# design.net
KiCad netlist of a schematic drawn in Altium Designer
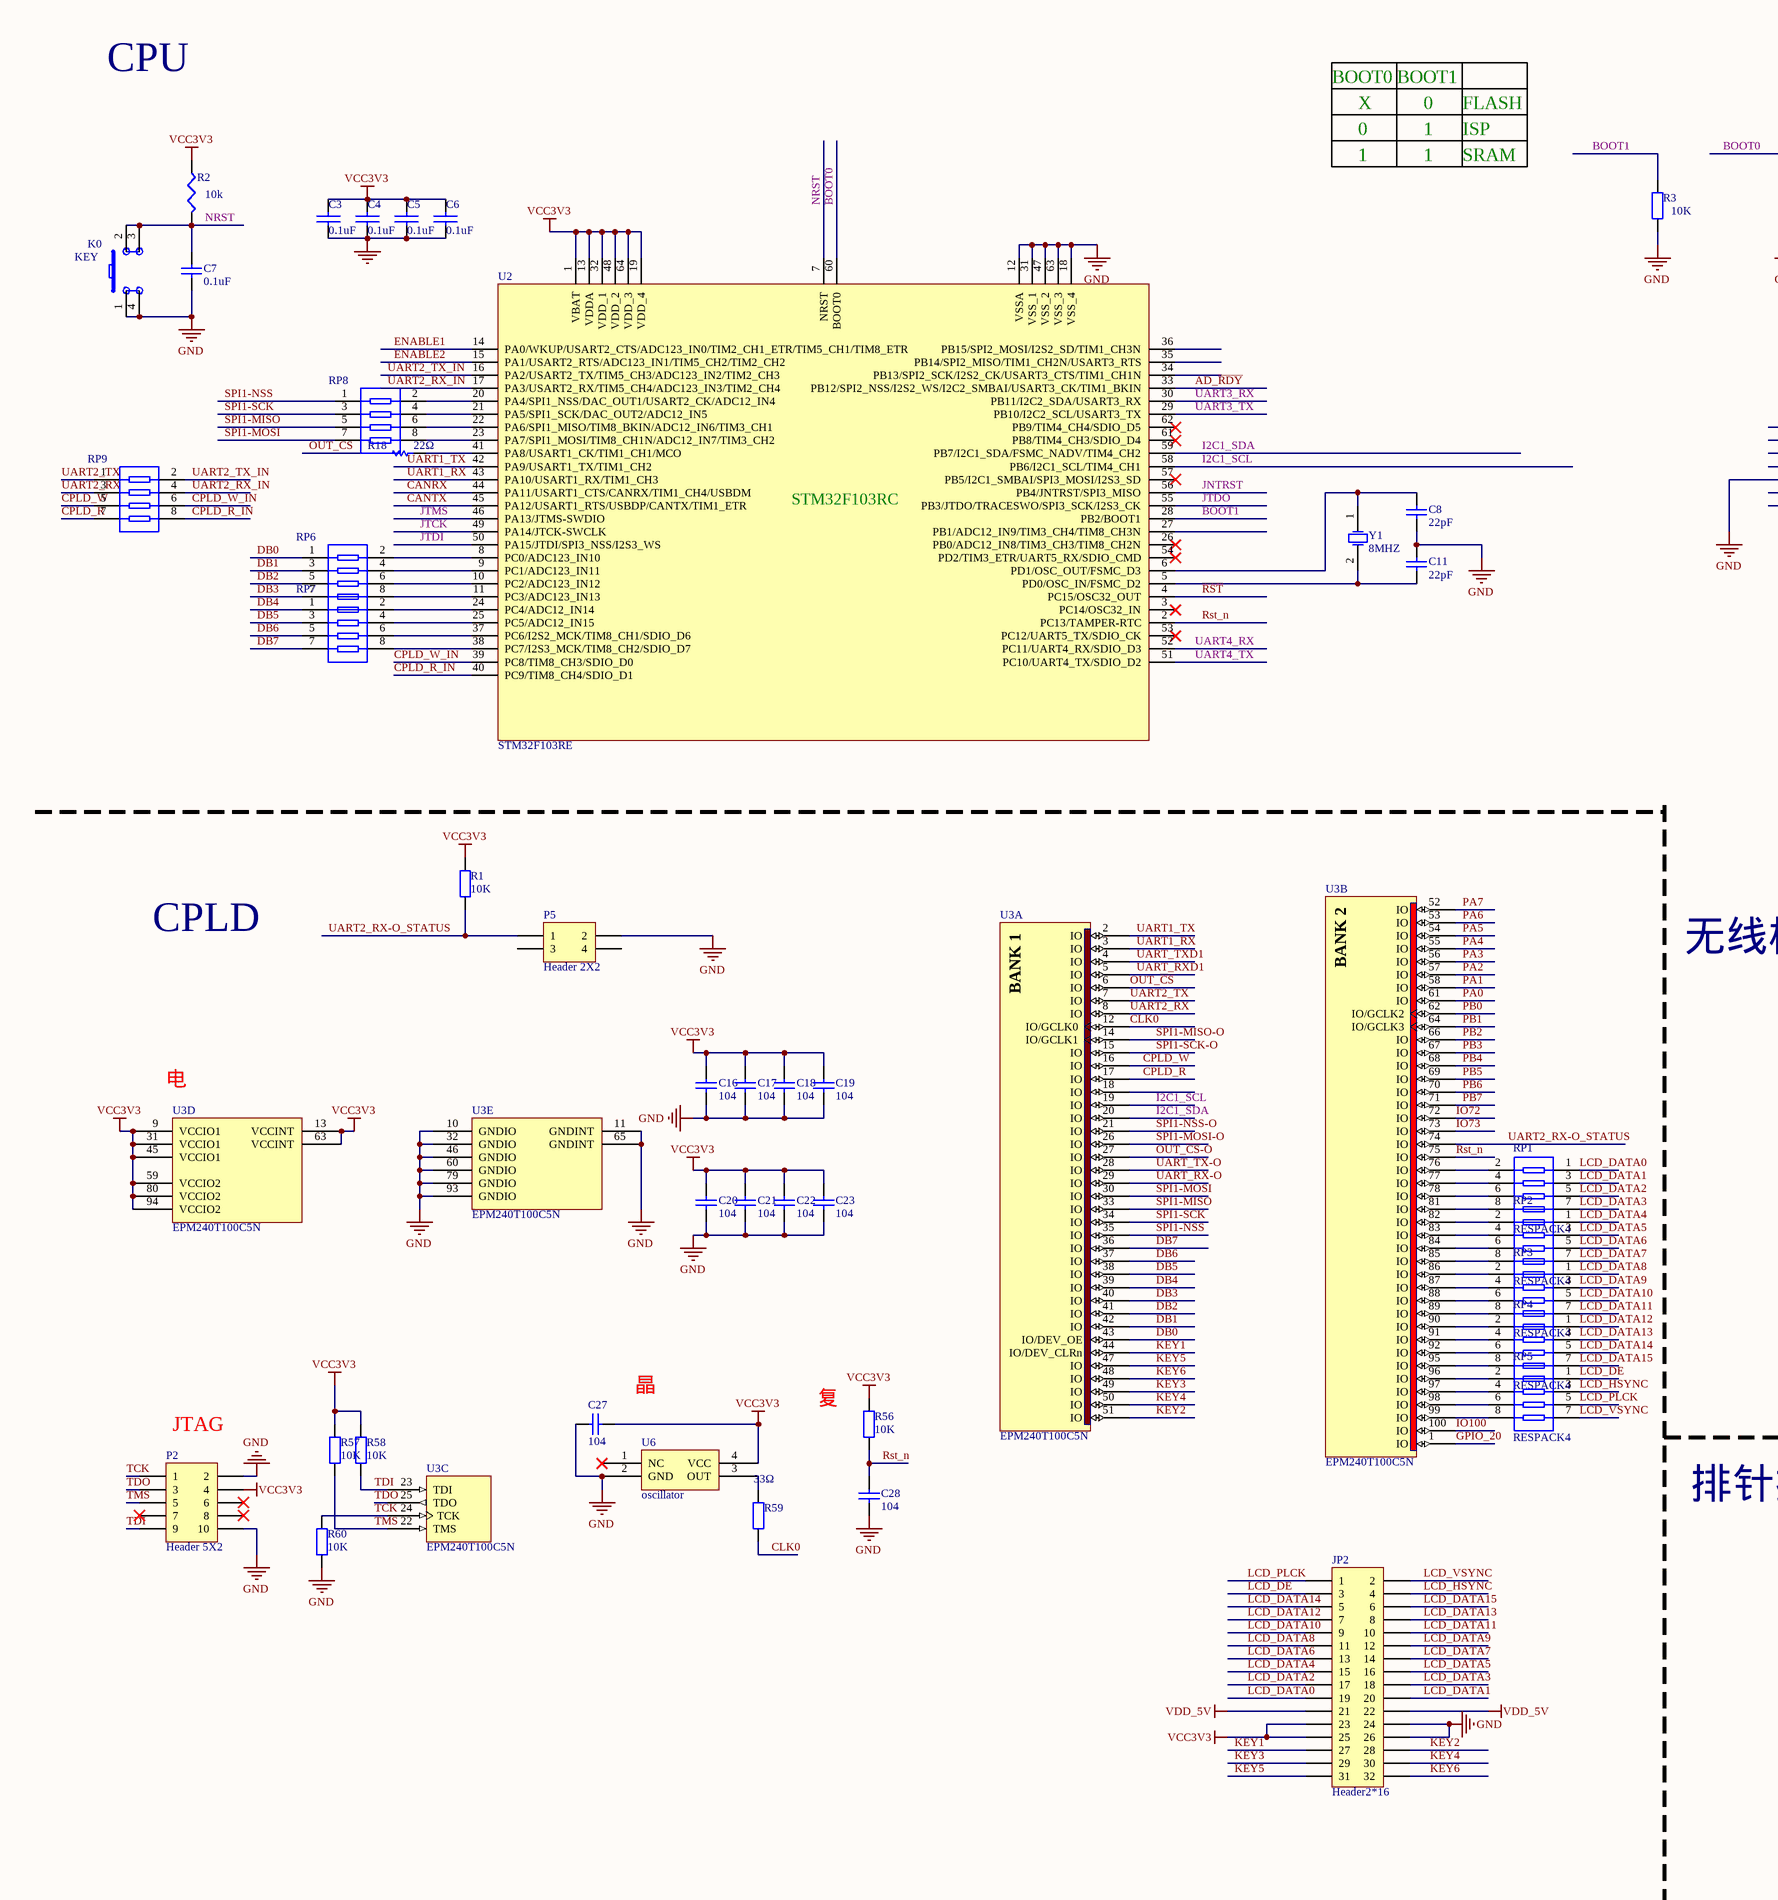
[diagram p0: 控制板.SchDoc, left]
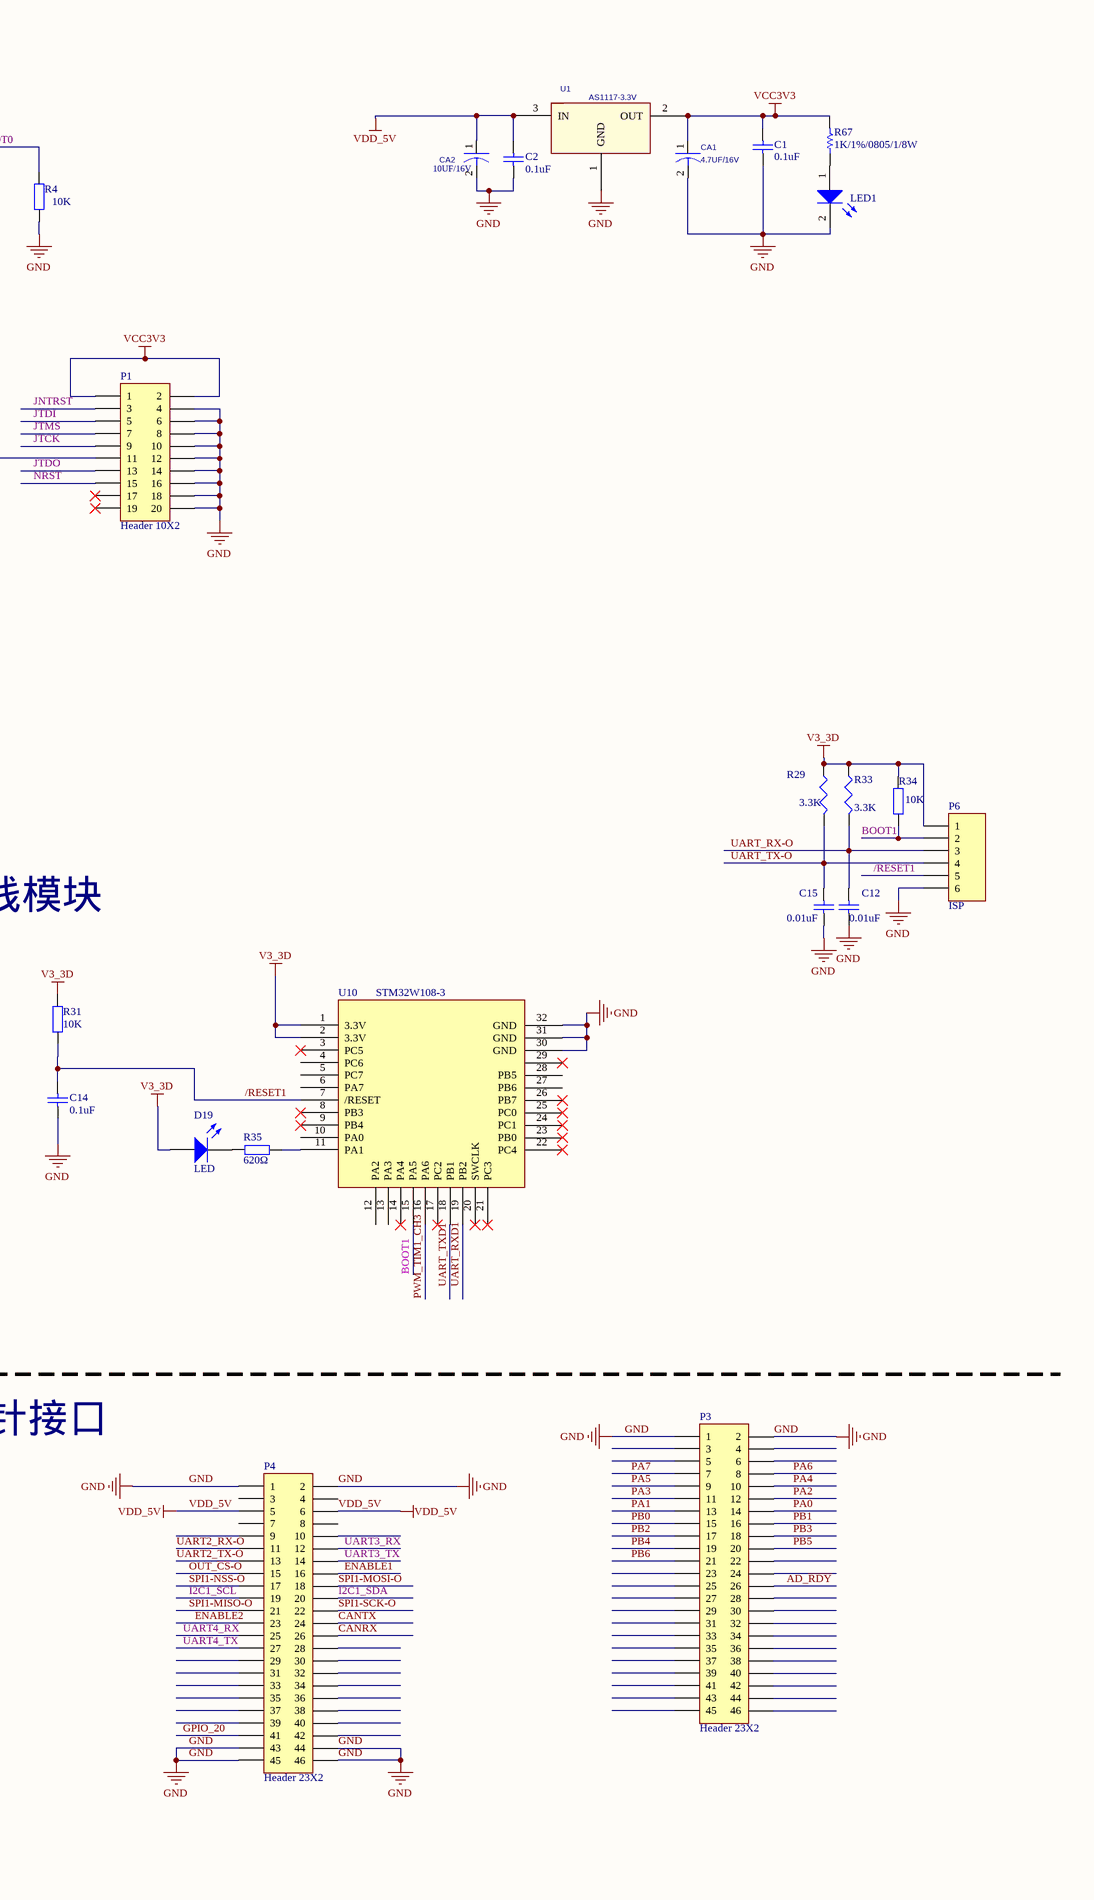
[diagram p1: 控制板.SchDoc, right]

(export (version "E")
  (design (tool "Eeschema 10.0.6"))
  (components
    (comp (ref "C1")
      (value "0.1uF")
      (footprint "C0805")
      (description "Capacitor")
      (fields (field (name "PUBLISHER") "Altium Limited"))
      (libsource (lib "Miscellaneous Devices") (part "Cap"))
    )
    (comp (ref "C2")
      (value "0.1uF")
      (footprint "C0805")
      (description "Capacitor")
      (fields (field (name "PUBLISHER") "Altium Limited"))
      (libsource (lib "Miscellaneous Devices") (part "Cap"))
    )
    (comp (ref "C3")
      (value "0.1uF")
      (footprint "C0805")
      (description "Capacitor")
      (libsource (lib "*") (part "Cap"))
    )
    (comp (ref "C4")
      (value "0.1uF")
      (footprint "C0805")
      (description "Capacitor")
      (libsource (lib "*") (part "Cap"))
    )
    (comp (ref "C5")
      (value "0.1uF")
      (footprint "C0805")
      (description "Capacitor")
      (libsource (lib "*") (part "Cap"))
    )
    (comp (ref "C6")
      (value "0.1uF")
      (footprint "C0805")
      (description "Capacitor")
      (libsource (lib "*") (part "Cap"))
    )
    (comp (ref "C7")
      (value "0.1uF")
      (footprint "C0805")
      (description "Capacitor")
      (fields (field (name "PUBLISHER") "Altium Limited"))
      (libsource (lib "Miscellaneous Devices") (part "Cap"))
    )
    (comp (ref "C8")
      (value "22pF")
      (footprint "C0805")
      (description "Capacitor")
      (fields (field (name "PUBLISHER") "Altium Limited"))
      (libsource (lib "Miscellaneous Devices") (part "Cap"))
    )
    (comp (ref "C11")
      (value "22pF")
      (footprint "C0805")
      (description "Capacitor")
      (fields (field (name "PUBLISHER") "Altium Limited"))
      (libsource (lib "Miscellaneous Devices") (part "Cap"))
    )
    (comp (ref "C12")
      (value "0.01uF")
      (footprint "C0805")
      (description "Capacitor")
      (fields (field (name "PUBLISHER") "Altium Limited"))
      (libsource (lib "Miscellaneous Devices") (part "Cap"))
    )
    (comp (ref "C14")
      (value "0.1uF")
      (footprint "C0805")
      (description "Capacitor")
      (fields (field (name "PUBLISHER") "Altium Limited"))
      (libsource (lib "Miscellaneous Devices") (part "Cap"))
    )
    (comp (ref "C15")
      (value "0.01uF")
      (footprint "C0805")
      (description "Capacitor")
      (fields (field (name "PUBLISHER") "Altium Limited"))
      (libsource (lib "Miscellaneous Devices") (part "Cap"))
    )
    (comp (ref "C16")
      (value "104")
      (footprint "C0805")
      (description "Capacitor")
      (fields (field (name "Comment") "0.1uF") (field (name "PUBLISHER") "Altium Limited"))
      (libsource (lib "Miscellaneous Devices") (part "Cap"))
    )
    (comp (ref "C17")
      (value "104")
      (footprint "C0805")
      (description "Capacitor")
      (fields (field (name "Comment") "0.1uF") (field (name "PUBLISHER") "Altium Limited"))
      (libsource (lib "Miscellaneous Devices") (part "Cap"))
    )
    (comp (ref "C18")
      (value "104")
      (footprint "C0805")
      (description "Capacitor")
      (fields (field (name "Comment") "0.1uF") (field (name "PUBLISHER") "Altium Limited"))
      (libsource (lib "Miscellaneous Devices") (part "Cap"))
    )
    (comp (ref "C19")
      (value "104")
      (footprint "C0805")
      (description "Capacitor")
      (fields (field (name "Comment") "0.1uF") (field (name "PUBLISHER") "Altium Limited"))
      (libsource (lib "Miscellaneous Devices") (part "Cap"))
    )
    (comp (ref "C20")
      (value "104")
      (footprint "C0805")
      (description "Capacitor")
      (fields (field (name "Comment") "0.1uF") (field (name "PUBLISHER") "Altium Limited"))
      (libsource (lib "Miscellaneous Devices") (part "Cap"))
    )
    (comp (ref "C21")
      (value "104")
      (footprint "C0805")
      (description "Capacitor")
      (fields (field (name "Comment") "0.1uF") (field (name "PUBLISHER") "Altium Limited"))
      (libsource (lib "Miscellaneous Devices") (part "Cap"))
    )
    (comp (ref "C22")
      (value "104")
      (footprint "C0805")
      (description "Capacitor")
      (fields (field (name "Comment") "0.1uF") (field (name "PUBLISHER") "Altium Limited"))
      (libsource (lib "Miscellaneous Devices") (part "Cap"))
    )
    (comp (ref "C23")
      (value "104")
      (footprint "C0805")
      (description "Capacitor")
      (fields (field (name "Comment") "0.1uF") (field (name "PUBLISHER") "Altium Limited"))
      (libsource (lib "Miscellaneous Devices") (part "Cap"))
    )
    (comp (ref "C27")
      (value "104")
      (footprint "C0805")
      (description "Capacitor")
      (fields (field (name "Comment") "0.1uF") (field (name "PUBLISHER") "Altium Limited"))
      (libsource (lib "Miscellaneous Devices") (part "Cap"))
    )
    (comp (ref "C28")
      (value "104")
      (footprint "C0805")
      (description "Capacitor")
      (fields (field (name "Comment") "0.1uF") (field (name "PUBLISHER") "Altium Limited"))
      (libsource (lib "Miscellaneous Devices") (part "Cap"))
    )
    (comp (ref "CA1") (value "4.7UF/16V") (footprint "3528cap") (libsource (lib "v3") (part "ECAP")))
    (comp (ref "CA2") (value "10UF/16V") (footprint "3528cap") (libsource (lib "v3") (part "ECAP")))
    (comp (ref "D19")
      (value "LED")
      (footprint "0805LED")
      (description "Typical BLUE SiC LED")
      (fields (field (name "PUBLISHER") "Altium Limited"))
      (libsource (lib "Miscellaneous Devices") (part "LED3"))
    )
    (comp (ref "JP2")
      (value "Header2*16")
      (footprint "PIN-S-2.54-2*16")
      (libsource (lib "SCHLIBRARIES") (part "Header2*16"))
    )
    (comp (ref "K0") (value "KEY") (footprint "KEY-DIP") (libsource (lib "Haze") (part "KEY")))
    (comp (ref "LED1")
      (value "0805/Green")
      (footprint "LED-0805")
      (fields (field (name "PART NUMBER") "ASD-0012AA"))
      (libsource (lib "浙江关西电机数据库") (part "LED"))
    )
    (comp (ref "P1")
      (value "Header 10X2")
      (footprint "IDC-20")
      (description "Header, 10-Pin, Dual row")
      (fields (field (name "PUBLISHER") "Altium Limited"))
      (libsource (lib "Miscellaneous Connectors") (part "Header 10X2"))
    )
    (comp (ref "P2")
      (value "Header 5X2")
      (footprint "IDC-10")
      (description "Header, 5-Pin, Dual row")
      (fields (field (name "PUBLISHER") "Altium Limited"))
      (libsource (lib "Miscellaneous Connectors") (part "Header 5X2"))
    )
    (comp (ref "P3")
      (value "Header 23X2")
      (footprint "HDR2X23")
      (description "Header, 23-Pin, Dual row")
      (fields (field (name "PUBLISHER") "Altium Limited"))
      (libsource (lib "dolphi_ecs") (part "Header 23X2"))
    )
    (comp (ref "P4")
      (value "Header 23X2")
      (footprint "HDR2X23")
      (description "Header, 23-Pin, Dual row")
      (fields (field (name "PUBLISHER") "Altium Limited"))
      (libsource (lib "dolphi_ecs") (part "Header 23X2"))
    )
    (comp (ref "P5")
      (value "Header 2X2")
      (footprint "SOP4")
      (description "拨码开关")
      (fields (field (name "PUBLISHER") "Altium Limited"))
      (libsource (lib "Miscellaneous Connectors") (part "Header 2X2"))
    )
    (comp (ref "P6")
      (value "ISP")
      (footprint "SIP-6B")
      (description "Header 6X1")
      (fields (field (name "PUBLISHER") "Altium Limited"))
      (libsource (lib "Miscellaneous Connectors") (part "Header 6"))
    )
    (comp (ref "R1")
      (value "10K")
      (footprint "R0805")
      (description "Resistor")
      (fields (field (name "PUBLISHER") "Altium Limited"))
      (libsource (lib "Miscellaneous Devices") (part "Res2"))
    )
    (comp (ref "R2")
      (value "10k")
      (footprint "R0805")
      (description "Resistor")
      (fields (field (name "PUBLISHER") "Altium Limited"))
      (libsource (lib "Miscellaneous Devices") (part "Res3"))
    )
    (comp (ref "R3")
      (value "10K")
      (footprint "R0805")
      (description "Resistor")
      (fields (field (name "PUBLISHER") "Altium Limited"))
      (libsource (lib "Miscellaneous Devices") (part "Res2"))
    )
    (comp (ref "R4")
      (value "10K")
      (footprint "R0805")
      (description "Resistor")
      (fields (field (name "PUBLISHER") "Altium Limited"))
      (libsource (lib "Miscellaneous Devices") (part "Res2"))
    )
    (comp (ref "R18")
      (value "22Ω")
      (footprint "R0805")
      (description "Semiconductor Resistor")
      (fields (field (name "PUBLISHER") "Altium Limited"))
      (libsource (lib "Miscellaneous Devices") (part "Res Semi"))
    )
    (comp (ref "R29")
      (value "3.3K")
      (footprint "R0805")
      (description "Resistor")
      (fields (field (name "PUBLISHER") "Altium Limited"))
      (libsource (lib "Miscellaneous Devices") (part "Res3"))
    )
    (comp (ref "R31")
      (value "10K")
      (footprint "0805")
      (description "Resistor")
      (fields (field (name "PUBLISHER") "Altium Limited"))
      (libsource (lib "Miscellaneous Devices") (part "Res2"))
    )
    (comp (ref "R33")
      (value "3.3K")
      (footprint "R0805")
      (description "Resistor")
      (fields (field (name "PUBLISHER") "Altium Limited"))
      (libsource (lib "Miscellaneous Devices") (part "Res3"))
    )
    (comp (ref "R34")
      (value "10K")
      (footprint "R0805")
      (description "Resistor")
      (fields (field (name "PUBLISHER") "Altium Limited"))
      (libsource (lib "Miscellaneous Devices") (part "Res2"))
    )
    (comp (ref "R35")
      (value "620Ω")
      (footprint "R0805")
      (description "R")
      (libsource (lib "Haze") (part "RES"))
    )
    (comp (ref "R56")
      (value "10K")
      (footprint "R0805")
      (description "Resistor")
      (fields (field (name "PUBLISHER") "Altium Limited"))
      (libsource (lib "Miscellaneous Devices") (part "Res2"))
    )
    (comp (ref "R57")
      (value "10K")
      (footprint "R0805")
      (description "Resistor")
      (fields (field (name "PUBLISHER") "Altium Limited"))
      (libsource (lib "Miscellaneous Devices") (part "Res2"))
    )
    (comp (ref "R58")
      (value "10K")
      (footprint "R0805")
      (description "Resistor")
      (fields (field (name "PUBLISHER") "Altium Limited"))
      (libsource (lib "Miscellaneous Devices") (part "Res2"))
    )
    (comp (ref "R59")
      (value "33Ω")
      (footprint "R0805")
      (description "Resistor")
      (fields (field (name "PUBLISHER") "Altium Limited"))
      (libsource (lib "Miscellaneous Devices") (part "Res2"))
    )
    (comp (ref "R60")
      (value "10K")
      (footprint "R0805")
      (description "Resistor")
      (fields (field (name "PUBLISHER") "Altium Limited"))
      (libsource (lib "Miscellaneous Devices") (part "Res2"))
    )
    (comp (ref "R67")
      (value "1K/1%/0805/1/8W")
      (footprint "R-0805")
      (fields (field (name "PART NUMBER") "ASR-0058AA"))
      (libsource (lib "浙江关西电机数据库") (part "RES_1"))
    )
    (comp (ref "RP1")
      (value "RESPACK4")
      (footprint "8P4R_0603")
      (description "22Ω")
      (libsource (lib "*") (part "RESPACK4"))
    )
    (comp (ref "RP2")
      (value "RESPACK4")
      (footprint "8P4R_0603")
      (description "22Ω")
      (libsource (lib "*") (part "RESPACK4"))
    )
    (comp (ref "RP3")
      (value "RESPACK4")
      (footprint "8P4R_0603")
      (description "22Ω")
      (libsource (lib "*") (part "RESPACK4"))
    )
    (comp (ref "RP4")
      (value "RESPACK4")
      (footprint "8P4R_0603")
      (description "22Ω")
      (libsource (lib "*") (part "RESPACK4"))
    )
    (comp (ref "RP5")
      (value "RESPACK4")
      (footprint "8P4R_0603")
      (description "22Ω")
      (libsource (lib "*") (part "RESPACK4"))
    )
    (comp (ref "RP6")
      (value "RESPACK4")
      (footprint "8P4R_0603")
      (description "22Ω")
      (libsource (lib "*") (part "RESPACK4"))
    )
    (comp (ref "RP7")
      (value "RESPACK4")
      (footprint "8P4R_0603")
      (description "22Ω")
      (libsource (lib "*") (part "RESPACK4"))
    )
    (comp (ref "RP8")
      (value "RESPACK4")
      (footprint "8P4R_0603")
      (description "22Ω")
      (libsource (lib "*") (part "RESPACK4"))
    )
    (comp (ref "RP9")
      (value "RESPACK4")
      (footprint "8P4R_0603")
      (description "22Ω")
      (libsource (lib "*") (part "RESPACK4"))
    )
    (comp (ref "U1") (value "AS1117-3.3V") (libsource (lib "v3") (part "AS1117")))
    (comp (ref "U2") (value "STM32F103RE") (footprint "LQFP64") (libsource (lib "MXJ") (part "STM32F103RE")))
    (comp (ref "U3")
      (value "EPM240T100C5N")
      (footprint "TQFP100_N")
      (fields (field (name "PUBLISHER") "Altium Limited"))
      (libsource (lib "Altera MAX II") (part "EPM240GT100C5N"))
    )
    (comp (ref "U6")
      (value "oscillator")
      (footprint "JZ-5032")
      (libsource (lib "Schlib1") (part "oscillator"))
    )
    (comp (ref "U10")
      (value "STM32W108-3")
      (footprint "STM32W108-3")
      (libsource (lib "STM32W108-3") (part "STM32W108-3"))
    )
    (comp (ref "Y1")
      (value "8MHZ")
      (footprint "XTAL")
      (description "Crystal Oscillator")
      (fields (field (name "PUBLISHER") "Altium Limited"))
      (libsource (lib "Miscellaneous Devices") (part "XTAL"))
    )
  )
  (nets
    (net (code "2") (name "/AD_~{RDY}") (class "Default")
      (node (ref "P3") (pin "26") (pinfunction "26_26") (pintype "passive"))
      (node (ref "U2") (pin "33") (pinfunction "PB12/SPI2_NSS/I2S2_WS/I2C2_SMBAI/USART3_CK/TIM1_BKIN_33") (pintype "passive"))
    )
    (net (code "3") (name "/BOOT0") (class "Default")
      (node (ref "R4") (pin "2") (pinfunction "2_2") (pintype "passive"))
      (node (ref "U2") (pin "60") (pinfunction "BOOT0_60") (pintype "passive"))
    )
    (net (code "4") (name "/BOOT1") (class "Default")
      (node (ref "P6") (pin "2") (pinfunction "2_2") (pintype "passive"))
      (node (ref "R3") (pin "2") (pinfunction "2_2") (pintype "passive"))
      (node (ref "R34") (pin "1") (pinfunction "1_1") (pintype "passive"))
      (node (ref "U10") (pin "15") (pinfunction "PA5_15") (pintype "passive"))
      (node (ref "U2") (pin "28") (pinfunction "PB2/BOOT1_28") (pintype "passive"))
    )
    (net (code "5") (name "/CANRX") (class "Default")
      (node (ref "P4") (pin "26") (pinfunction "26_26") (pintype "passive"))
      (node (ref "U2") (pin "44") (pinfunction "PA11/USART1_CTS/CANRX/TIM1_CH4/USBDM_44") (pintype "passive"))
    )
    (net (code "6") (name "/CANTX") (class "Default")
      (node (ref "P4") (pin "24") (pinfunction "24_24") (pintype "passive"))
      (node (ref "U2") (pin "45") (pinfunction "PA12/USART1_RTS/USBDP/CANTX/TIM1_ETR_45") (pintype "passive"))
    )
    (net (code "7") (name "/CLK0") (class "Default")
      (node (ref "R59") (pin "1") (pinfunction "1_1") (pintype "passive"))
      (node (ref "U3") (pin "12") (pinfunction "IO/GCLK0_12") (pintype "bidirectional"))
    )
    (net (code "8") (name "/CPLD_R") (class "Default")
      (node (ref "RP9") (pin "7") (pinfunction "7_7") (pintype "passive"))
      (node (ref "U3") (pin "17") (pinfunction "IO_17") (pintype "bidirectional"))
    )
    (net (code "9") (name "/CPLD_R_IN") (class "Default")
      (node (ref "RP9") (pin "8") (pinfunction "8_8") (pintype "passive"))
      (node (ref "U2") (pin "40") (pinfunction "PC9/TIM8_CH4/SDIO_D1_40") (pintype "passive"))
    )
    (net (code "10") (name "/CPLD_W") (class "Default")
      (node (ref "RP9") (pin "5") (pinfunction "5_5") (pintype "passive"))
      (node (ref "U3") (pin "16") (pinfunction "IO_16") (pintype "bidirectional"))
    )
    (net (code "11") (name "/CPLD_W_IN") (class "Default")
      (node (ref "RP9") (pin "6") (pinfunction "6_6") (pintype "passive"))
      (node (ref "U2") (pin "39") (pinfunction "PC8/TIM8_CH3/SDIO_D0_39") (pintype "passive"))
    )
    (net (code "12") (name "/DB0") (class "Default")
      (node (ref "RP6") (pin "1") (pinfunction "1_1") (pintype "passive"))
      (node (ref "U3") (pin "43") (pinfunction "IO/DEV_OE_43") (pintype "bidirectional"))
    )
    (net (code "13") (name "/DB1") (class "Default")
      (node (ref "RP6") (pin "3") (pinfunction "3_3") (pintype "passive"))
      (node (ref "U3") (pin "42") (pinfunction "IO_42") (pintype "bidirectional"))
    )
    (net (code "14") (name "/DB2") (class "Default")
      (node (ref "RP6") (pin "5") (pinfunction "5_5") (pintype "passive"))
      (node (ref "U3") (pin "41") (pinfunction "IO_41") (pintype "bidirectional"))
    )
    (net (code "15") (name "/DB3") (class "Default")
      (node (ref "RP6") (pin "7") (pinfunction "7_7") (pintype "passive"))
      (node (ref "U3") (pin "40") (pinfunction "IO_40") (pintype "bidirectional"))
    )
    (net (code "16") (name "/DB4") (class "Default")
      (node (ref "RP7") (pin "1") (pinfunction "1_1") (pintype "passive"))
      (node (ref "U3") (pin "39") (pinfunction "IO_39") (pintype "bidirectional"))
    )
    (net (code "17") (name "/DB5") (class "Default")
      (node (ref "RP7") (pin "3") (pinfunction "3_3") (pintype "passive"))
      (node (ref "U3") (pin "38") (pinfunction "IO_38") (pintype "bidirectional"))
    )
    (net (code "18") (name "/DB6") (class "Default")
      (node (ref "RP7") (pin "5") (pinfunction "5_5") (pintype "passive"))
      (node (ref "U3") (pin "37") (pinfunction "IO_37") (pintype "bidirectional"))
    )
    (net (code "19") (name "/DB7") (class "Default")
      (node (ref "RP7") (pin "7") (pinfunction "7_7") (pintype "passive"))
      (node (ref "U3") (pin "36") (pinfunction "IO_36") (pintype "bidirectional"))
    )
    (net (code "20") (name "/ENABLE1") (class "Default")
      (node (ref "P4") (pin "16") (pinfunction "16_16") (pintype "passive"))
      (node (ref "U2") (pin "14") (pinfunction "PA0/WKUP/USART2_CTS/ADC123_IN0/TIM2_CH1_ETR/TIM5_CH1/TIM8_ETR_14") (pintype "passive"))
    )
    (net (code "21") (name "/ENABLE2") (class "Default")
      (node (ref "P4") (pin "23") (pinfunction "23_23") (pintype "passive"))
      (node (ref "U2") (pin "15") (pinfunction "PA1/USART2_RTS/ADC123_IN1/TIM5_CH2/TIM2_CH2_15") (pintype "passive"))
    )
    (net (code "22") (name "/GPIO_20") (class "Default")
      (node (ref "P4") (pin "41") (pinfunction "41_41") (pintype "passive"))
      (node (ref "U3") (pin "1") (pinfunction "IO_1") (pintype "bidirectional"))
    )
    (net (code "23") (name "/I2C1_SCL") (class "Default")
      (node (ref "P4") (pin "19") (pinfunction "19_19") (pintype "passive"))
      (node (ref "U2") (pin "58") (pinfunction "PB6/I2C1_SCL/TIM4_CH1_58") (pintype "passive"))
      (node (ref "U3") (pin "19") (pinfunction "IO_19") (pintype "bidirectional"))
    )
    (net (code "24") (name "/I2C1_SDA") (class "Default")
      (node (ref "P4") (pin "20") (pinfunction "20_20") (pintype "passive"))
      (node (ref "U2") (pin "59") (pinfunction "PB7/I2C1_SDA/FSMC_NADV/TIM4_CH2_59") (pintype "passive"))
      (node (ref "U3") (pin "20") (pinfunction "IO_20") (pintype "bidirectional"))
    )
    (net (code "25") (name "/IO72") (class "Default")
      (node (ref "U3") (pin "72") (pinfunction "IO_72") (pintype "bidirectional"))
    )
    (net (code "26") (name "/IO73") (class "Default")
      (node (ref "U3") (pin "73") (pinfunction "IO_73") (pintype "bidirectional"))
    )
    (net (code "27") (name "/IO100") (class "Default")
      (node (ref "U3") (pin "100") (pinfunction "IO_100") (pintype "bidirectional"))
    )
    (net (code "28") (name "/JNTRST") (class "Default")
      (node (ref "P1") (pin "3") (pinfunction "3_3") (pintype "passive"))
      (node (ref "U2") (pin "56") (pinfunction "PB4/JNTRST/SPI3_MISO_56") (pintype "passive"))
    )
    (net (code "29") (name "/JTCK") (class "Default")
      (node (ref "P1") (pin "9") (pinfunction "9_9") (pintype "passive"))
      (node (ref "U2") (pin "49") (pinfunction "PA14/JTCK-SWCLK_49") (pintype "passive"))
    )
    (net (code "30") (name "/JTDI") (class "Default")
      (node (ref "P1") (pin "5") (pinfunction "5_5") (pintype "passive"))
      (node (ref "U2") (pin "50") (pinfunction "PA15/JTDI/SPI3_NSS/I2S3_WS_50") (pintype "passive"))
    )
    (net (code "31") (name "/JTDO") (class "Default")
      (node (ref "P1") (pin "13") (pinfunction "13_13") (pintype "passive"))
      (node (ref "U2") (pin "55") (pinfunction "PB3/JTDO/TRACESWO/SPI3_SCK/I2S3_CK_55") (pintype "passive"))
    )
    (net (code "32") (name "/JTMS") (class "Default")
      (node (ref "P1") (pin "7") (pinfunction "7_7") (pintype "passive"))
      (node (ref "U2") (pin "46") (pinfunction "PA13/JTMS-SWDIO_46") (pintype "passive"))
    )
    (net (code "33") (name "/KEY1") (class "Default")
      (node (ref "JP2") (pin "27") (pinfunction "27_27") (pintype "passive"))
      (node (ref "U3") (pin "44") (pinfunction "IO/DEV_CLRn_44") (pintype "bidirectional"))
    )
    (net (code "34") (name "/KEY2") (class "Default")
      (node (ref "JP2") (pin "28") (pinfunction "28_28") (pintype "passive"))
      (node (ref "U3") (pin "51") (pinfunction "IO_51") (pintype "bidirectional"))
    )
    (net (code "35") (name "/KEY3") (class "Default")
      (node (ref "JP2") (pin "29") (pinfunction "29_29") (pintype "passive"))
      (node (ref "U3") (pin "49") (pinfunction "IO_49") (pintype "bidirectional"))
    )
    (net (code "36") (name "/KEY4") (class "Default")
      (node (ref "JP2") (pin "30") (pinfunction "30_30") (pintype "passive"))
      (node (ref "U3") (pin "50") (pinfunction "IO_50") (pintype "bidirectional"))
    )
    (net (code "37") (name "/KEY5") (class "Default")
      (node (ref "JP2") (pin "31") (pinfunction "31_31") (pintype "passive"))
      (node (ref "U3") (pin "47") (pinfunction "IO_47") (pintype "bidirectional"))
    )
    (net (code "38") (name "/KEY6") (class "Default")
      (node (ref "JP2") (pin "32") (pinfunction "32_32") (pintype "passive"))
      (node (ref "U3") (pin "48") (pinfunction "IO_48") (pintype "bidirectional"))
    )
    (net (code "39") (name "/LCD_DATA0") (class "Default")
      (node (ref "JP2") (pin "19") (pinfunction "19_19") (pintype "passive"))
      (node (ref "RP1") (pin "1") (pinfunction "1_1") (pintype "passive"))
    )
    (net (code "40") (name "/LCD_DATA1") (class "Default")
      (node (ref "JP2") (pin "20") (pinfunction "20_20") (pintype "passive"))
      (node (ref "RP1") (pin "3") (pinfunction "3_3") (pintype "passive"))
    )
    (net (code "41") (name "/LCD_DATA2") (class "Default")
      (node (ref "JP2") (pin "17") (pinfunction "17_17") (pintype "passive"))
      (node (ref "RP1") (pin "5") (pinfunction "5_5") (pintype "passive"))
    )
    (net (code "42") (name "/LCD_DATA3") (class "Default")
      (node (ref "JP2") (pin "18") (pinfunction "18_18") (pintype "passive"))
      (node (ref "RP1") (pin "7") (pinfunction "7_7") (pintype "passive"))
    )
    (net (code "43") (name "/LCD_DATA4") (class "Default")
      (node (ref "JP2") (pin "15") (pinfunction "15_15") (pintype "passive"))
      (node (ref "RP2") (pin "1") (pinfunction "1_1") (pintype "passive"))
    )
    (net (code "44") (name "/LCD_DATA5") (class "Default")
      (node (ref "JP2") (pin "16") (pinfunction "16_16") (pintype "passive"))
      (node (ref "RP2") (pin "3") (pinfunction "3_3") (pintype "passive"))
    )
    (net (code "45") (name "/LCD_DATA6") (class "Default")
      (node (ref "JP2") (pin "13") (pinfunction "13_13") (pintype "passive"))
      (node (ref "RP2") (pin "5") (pinfunction "5_5") (pintype "passive"))
    )
    (net (code "46") (name "/LCD_DATA7") (class "Default")
      (node (ref "JP2") (pin "14") (pinfunction "14_14") (pintype "passive"))
      (node (ref "RP2") (pin "7") (pinfunction "7_7") (pintype "passive"))
    )
    (net (code "47") (name "/LCD_DATA8") (class "Default")
      (node (ref "JP2") (pin "11") (pinfunction "11_11") (pintype "passive"))
      (node (ref "RP3") (pin "1") (pinfunction "1_1") (pintype "passive"))
    )
    (net (code "48") (name "/LCD_DATA9") (class "Default")
      (node (ref "JP2") (pin "12") (pinfunction "12_12") (pintype "passive"))
      (node (ref "RP3") (pin "3") (pinfunction "3_3") (pintype "passive"))
    )
    (net (code "49") (name "/LCD_DATA10") (class "Default")
      (node (ref "JP2") (pin "9") (pinfunction "9_9") (pintype "passive"))
      (node (ref "RP3") (pin "5") (pinfunction "5_5") (pintype "passive"))
    )
    (net (code "50") (name "/LCD_DATA11") (class "Default")
      (node (ref "JP2") (pin "10") (pinfunction "10_10") (pintype "passive"))
      (node (ref "RP3") (pin "7") (pinfunction "7_7") (pintype "passive"))
    )
    (net (code "51") (name "/LCD_DATA12") (class "Default")
      (node (ref "JP2") (pin "7") (pinfunction "7_7") (pintype "passive"))
      (node (ref "RP4") (pin "1") (pinfunction "1_1") (pintype "passive"))
    )
    (net (code "52") (name "/LCD_DATA13") (class "Default")
      (node (ref "JP2") (pin "8") (pinfunction "8_8") (pintype "passive"))
      (node (ref "RP4") (pin "3") (pinfunction "3_3") (pintype "passive"))
    )
    (net (code "53") (name "/LCD_DATA14") (class "Default")
      (node (ref "JP2") (pin "5") (pinfunction "5_5") (pintype "passive"))
      (node (ref "RP4") (pin "5") (pinfunction "5_5") (pintype "passive"))
    )
    (net (code "54") (name "/LCD_DATA15") (class "Default")
      (node (ref "JP2") (pin "6") (pinfunction "6_6") (pintype "passive"))
      (node (ref "RP4") (pin "7") (pinfunction "7_7") (pintype "passive"))
    )
    (net (code "55") (name "/LCD_DE") (class "Default")
      (node (ref "JP2") (pin "3") (pinfunction "3_3") (pintype "passive"))
      (node (ref "RP5") (pin "1") (pinfunction "1_1") (pintype "passive"))
    )
    (net (code "56") (name "/LCD_HSYNC") (class "Default")
      (node (ref "JP2") (pin "4") (pinfunction "4_4") (pintype "passive"))
      (node (ref "RP5") (pin "3") (pinfunction "3_3") (pintype "passive"))
    )
    (net (code "57") (name "/LCD_PLCK") (class "Default")
      (node (ref "JP2") (pin "1") (pinfunction "1_1") (pintype "passive"))
      (node (ref "RP5") (pin "5") (pinfunction "5_5") (pintype "passive"))
    )
    (net (code "58") (name "/LCD_VSYNC") (class "Default")
      (node (ref "JP2") (pin "2") (pinfunction "2_2") (pintype "passive"))
      (node (ref "RP5") (pin "7") (pinfunction "7_7") (pintype "passive"))
    )
    (net (code "59") (name "/NRST") (class "Default")
      (node (ref "C7") (pin "2") (pinfunction "2_2") (pintype "passive"))
      (node (ref "K0") (pin "2") (pintype "passive"))
      (node (ref "K0") (pin "3") (pintype "passive"))
      (node (ref "P1") (pin "15") (pinfunction "15_15") (pintype "passive"))
      (node (ref "R2") (pin "2") (pinfunction "2_2") (pintype "passive"))
      (node (ref "U2") (pin "7") (pinfunction "NRST_7") (pintype "passive"))
    )
    (net (code "60") (name "/OUT_~{CS}") (class "Default")
      (node (ref "R18") (pin "1") (pinfunction "1_1") (pintype "passive"))
      (node (ref "U3") (pin "6") (pinfunction "IO_6") (pintype "bidirectional"))
    )
    (net (code "61") (name "/OUT_~{CS}-O") (class "Default")
      (node (ref "P4") (pin "15") (pinfunction "15_15") (pintype "passive"))
      (node (ref "U3") (pin "27") (pinfunction "IO_27") (pintype "bidirectional"))
    )
    (net (code "62") (name "/PA0") (class "Default")
      (node (ref "P3") (pin "14") (pinfunction "14_14") (pintype "passive"))
      (node (ref "U3") (pin "61") (pinfunction "IO_61") (pintype "bidirectional"))
    )
    (net (code "63") (name "/PA1") (class "Default")
      (node (ref "P3") (pin "13") (pinfunction "13_13") (pintype "passive"))
      (node (ref "U3") (pin "58") (pinfunction "IO_58") (pintype "bidirectional"))
    )
    (net (code "64") (name "/PA2") (class "Default")
      (node (ref "P3") (pin "12") (pinfunction "12_12") (pintype "passive"))
      (node (ref "U3") (pin "57") (pinfunction "IO_57") (pintype "bidirectional"))
    )
    (net (code "65") (name "/PA3") (class "Default")
      (node (ref "P3") (pin "11") (pinfunction "11_11") (pintype "passive"))
      (node (ref "U3") (pin "56") (pinfunction "IO_56") (pintype "bidirectional"))
    )
    (net (code "66") (name "/PA4") (class "Default")
      (node (ref "P3") (pin "10") (pinfunction "10_10") (pintype "passive"))
      (node (ref "U3") (pin "55") (pinfunction "IO_55") (pintype "bidirectional"))
    )
    (net (code "67") (name "/PA5") (class "Default")
      (node (ref "P3") (pin "9") (pinfunction "9_9") (pintype "passive"))
      (node (ref "U3") (pin "54") (pinfunction "IO_54") (pintype "bidirectional"))
    )
    (net (code "68") (name "/PA6") (class "Default")
      (node (ref "P3") (pin "8") (pinfunction "8_8") (pintype "passive"))
      (node (ref "U3") (pin "53") (pinfunction "IO_53") (pintype "bidirectional"))
    )
    (net (code "69") (name "/PA7") (class "Default")
      (node (ref "P3") (pin "7") (pinfunction "7_7") (pintype "passive"))
      (node (ref "U3") (pin "52") (pinfunction "IO_52") (pintype "bidirectional"))
    )
    (net (code "70") (name "/PB0") (class "Default")
      (node (ref "P3") (pin "15") (pinfunction "15_15") (pintype "passive"))
      (node (ref "U3") (pin "62") (pinfunction "IO/GCLK2_62") (pintype "bidirectional"))
    )
    (net (code "71") (name "/PB1") (class "Default")
      (node (ref "P3") (pin "16") (pinfunction "16_16") (pintype "passive"))
      (node (ref "U3") (pin "64") (pinfunction "IO/GCLK3_64") (pintype "bidirectional"))
    )
    (net (code "72") (name "/PB2") (class "Default")
      (node (ref "P3") (pin "17") (pinfunction "17_17") (pintype "passive"))
      (node (ref "U3") (pin "66") (pinfunction "IO_66") (pintype "bidirectional"))
    )
    (net (code "73") (name "/PB3") (class "Default")
      (node (ref "P3") (pin "18") (pinfunction "18_18") (pintype "passive"))
      (node (ref "U3") (pin "67") (pinfunction "IO_67") (pintype "bidirectional"))
    )
    (net (code "74") (name "/PB4") (class "Default")
      (node (ref "P3") (pin "19") (pinfunction "19_19") (pintype "passive"))
      (node (ref "U3") (pin "68") (pinfunction "IO_68") (pintype "bidirectional"))
    )
    (net (code "75") (name "/PB5") (class "Default")
      (node (ref "P3") (pin "20") (pinfunction "20_20") (pintype "passive"))
      (node (ref "U3") (pin "69") (pinfunction "IO_69") (pintype "bidirectional"))
    )
    (net (code "76") (name "/PB6") (class "Default")
      (node (ref "P3") (pin "21") (pinfunction "21_21") (pintype "passive"))
      (node (ref "U3") (pin "70") (pinfunction "IO_70") (pintype "bidirectional"))
    )
    (net (code "77") (name "/PB7") (class "Default")
      (node (ref "U3") (pin "71") (pinfunction "IO_71") (pintype "bidirectional"))
    )
    (net (code "78") (name "/PWM_TIM1_CH3") (class "Default")
      (node (ref "U10") (pin "16") (pinfunction "PA6_16") (pintype "passive"))
    )
    (net (code "79") (name "/Rst_n") (class "Default")
      (node (ref "C28") (pin "2") (pinfunction "2_2") (pintype "passive"))
      (node (ref "R56") (pin "1") (pinfunction "1_1") (pintype "passive"))
      (node (ref "U2") (pin "2") (pinfunction "PC13/TAMPER-RTC_2") (pintype "passive"))
      (node (ref "U3") (pin "75") (pinfunction "IO_75") (pintype "bidirectional"))
    )
    (net (code "80") (name "/SPI1-MISO") (class "Default")
      (node (ref "RP8") (pin "5") (pinfunction "5_5") (pintype "passive"))
      (node (ref "U3") (pin "33") (pinfunction "IO_33") (pintype "bidirectional"))
    )
    (net (code "81") (name "/SPI1-MISO-O") (class "Default")
      (node (ref "P4") (pin "21") (pinfunction "21_21") (pintype "passive"))
      (node (ref "U3") (pin "14") (pinfunction "IO/GCLK1_14") (pintype "bidirectional"))
    )
    (net (code "82") (name "/SPI1-MOSI") (class "Default")
      (node (ref "RP8") (pin "7") (pinfunction "7_7") (pintype "passive"))
      (node (ref "U3") (pin "30") (pinfunction "IO_30") (pintype "bidirectional"))
    )
    (net (code "83") (name "/SPI1-MOSI-O") (class "Default")
      (node (ref "P4") (pin "18") (pinfunction "18_18") (pintype "passive"))
      (node (ref "U3") (pin "26") (pinfunction "IO_26") (pintype "bidirectional"))
    )
    (net (code "84") (name "/SPI1-NSS") (class "Default")
      (node (ref "RP8") (pin "1") (pinfunction "1_1") (pintype "passive"))
      (node (ref "U3") (pin "35") (pinfunction "IO_35") (pintype "bidirectional"))
    )
    (net (code "85") (name "/SPI1-NSS-O") (class "Default")
      (node (ref "P4") (pin "17") (pinfunction "17_17") (pintype "passive"))
      (node (ref "U3") (pin "21") (pinfunction "IO_21") (pintype "bidirectional"))
    )
    (net (code "86") (name "/SPI1-SCK") (class "Default")
      (node (ref "RP8") (pin "3") (pinfunction "3_3") (pintype "passive"))
      (node (ref "U3") (pin "34") (pinfunction "IO_34") (pintype "bidirectional"))
    )
    (net (code "87") (name "/SPI1-SCK-O") (class "Default")
      (node (ref "P4") (pin "22") (pinfunction "22_22") (pintype "passive"))
      (node (ref "U3") (pin "15") (pinfunction "IO_15") (pintype "bidirectional"))
    )
    (net (code "88") (name "/TCK") (class "Default")
      (node (ref "P2") (pin "1") (pinfunction "1_1") (pintype "passive"))
      (node (ref "R60") (pin "2") (pinfunction "2_2") (pintype "passive"))
      (node (ref "U3") (pin "24") (pinfunction "TCK_24") (pintype "input"))
    )
    (net (code "89") (name "/TDI") (class "Default")
      (node (ref "P2") (pin "9") (pinfunction "9_9") (pintype "passive"))
      (node (ref "R58") (pin "1") (pinfunction "1_1") (pintype "passive"))
      (node (ref "U3") (pin "23") (pinfunction "TDI_23") (pintype "input"))
    )
    (net (code "90") (name "/TDO") (class "Default")
      (node (ref "P2") (pin "3") (pinfunction "3_3") (pintype "passive"))
      (node (ref "U3") (pin "25") (pinfunction "TDO_25") (pintype "output"))
    )
    (net (code "91") (name "/TMS") (class "Default")
      (node (ref "P2") (pin "5") (pinfunction "5_5") (pintype "passive"))
      (node (ref "R57") (pin "1") (pinfunction "1_1") (pintype "passive"))
      (node (ref "U3") (pin "22") (pinfunction "TMS_22") (pintype "input"))
    )
    (net (code "92") (name "/UART1_RX") (class "Default")
      (node (ref "U2") (pin "43") (pinfunction "PA10/USART1_RX/TIM1_CH3_43") (pintype "passive"))
      (node (ref "U3") (pin "3") (pinfunction "IO_3") (pintype "bidirectional"))
    )
    (net (code "93") (name "/UART1_TX") (class "Default")
      (node (ref "U2") (pin "42") (pinfunction "PA9/USART1_TX/TIM1_CH2_42") (pintype "passive"))
      (node (ref "U3") (pin "2") (pinfunction "IO_2") (pintype "bidirectional"))
    )
    (net (code "94") (name "/UART2_RX") (class "Default")
      (node (ref "RP9") (pin "3") (pinfunction "3_3") (pintype "passive"))
      (node (ref "U3") (pin "8") (pinfunction "IO_8") (pintype "bidirectional"))
    )
    (net (code "95") (name "/UART2_RX-O") (class "Default")
      (node (ref "P4") (pin "11") (pinfunction "11_11") (pintype "passive"))
    )
    (net (code "96") (name "/UART2_RX-O_STATUS") (class "Default")
      (node (ref "P5") (pin "1") (pinfunction "1_1") (pintype "passive"))
      (node (ref "R1") (pin "1") (pinfunction "1_1") (pintype "passive"))
      (node (ref "U3") (pin "74") (pinfunction "IO_74") (pintype "bidirectional"))
    )
    (net (code "97") (name "/UART2_RX_IN") (class "Default")
      (node (ref "RP9") (pin "4") (pinfunction "4_4") (pintype "passive"))
      (node (ref "U2") (pin "17") (pinfunction "PA3/USART2_RX/TIM5_CH4/ADC123_IN3/TIM2_CH4_17") (pintype "passive"))
    )
    (net (code "98") (name "/UART2_TX") (class "Default")
      (node (ref "RP9") (pin "1") (pinfunction "1_1") (pintype "passive"))
      (node (ref "U3") (pin "7") (pinfunction "IO_7") (pintype "bidirectional"))
    )
    (net (code "99") (name "/UART2_TX-O") (class "Default")
      (node (ref "P4") (pin "13") (pinfunction "13_13") (pintype "passive"))
    )
    (net (code "100") (name "/UART2_TX_IN") (class "Default")
      (node (ref "RP9") (pin "2") (pinfunction "2_2") (pintype "passive"))
      (node (ref "U2") (pin "16") (pinfunction "PA2/USART2_TX/TIM5_CH3/ADC123_IN2/TIM2_CH3_16") (pintype "passive"))
    )
    (net (code "101") (name "/UART3_RX") (class "Default")
      (node (ref "P4") (pin "12") (pinfunction "12_12") (pintype "passive"))
      (node (ref "U2") (pin "30") (pinfunction "PB11/I2C2_SDA/USART3_RX_30") (pintype "passive"))
    )
    (net (code "102") (name "/UART3_TX") (class "Default")
      (node (ref "P4") (pin "14") (pinfunction "14_14") (pintype "passive"))
      (node (ref "U2") (pin "29") (pinfunction "PB10/I2C2_SCL/USART3_TX_29") (pintype "passive"))
    )
    (net (code "103") (name "/UART4_RX") (class "Default")
      (node (ref "P4") (pin "25") (pinfunction "25_25") (pintype "passive"))
      (node (ref "U2") (pin "52") (pinfunction "PC11/UART4_RX/SDIO_D3_52") (pintype "passive"))
    )
    (net (code "104") (name "/UART4_TX") (class "Default")
      (node (ref "P4") (pin "27") (pinfunction "27_27") (pintype "passive"))
      (node (ref "U2") (pin "51") (pinfunction "PC10/UART4_TX/SDIO_D2_51") (pintype "passive"))
    )
    (net (code "105") (name "/UART_RX-O") (class "Default")
      (node (ref "C12") (pin "2") (pinfunction "2_2") (pintype "passive"))
      (node (ref "P6") (pin "3") (pinfunction "3_3") (pintype "passive"))
      (node (ref "R33") (pin "2") (pinfunction "2_2") (pintype "passive"))
      (node (ref "U3") (pin "29") (pinfunction "IO_29") (pintype "bidirectional"))
    )
    (net (code "106") (name "/UART_RXD1") (class "Default")
      (node (ref "U10") (pin "19") (pinfunction "PB2_19") (pintype "passive"))
      (node (ref "U3") (pin "5") (pinfunction "IO_5") (pintype "bidirectional"))
    )
    (net (code "107") (name "/UART_TX-O") (class "Default")
      (node (ref "C15") (pin "2") (pinfunction "2_2") (pintype "passive"))
      (node (ref "P6") (pin "4") (pinfunction "4_4") (pintype "passive"))
      (node (ref "R29") (pin "2") (pinfunction "2_2") (pintype "passive"))
      (node (ref "U3") (pin "28") (pinfunction "IO_28") (pintype "bidirectional"))
    )
    (net (code "108") (name "/UART_TXD1") (class "Default")
      (node (ref "U10") (pin "18") (pinfunction "PB1_18") (pintype "passive"))
      (node (ref "U3") (pin "4") (pinfunction "IO_4") (pintype "bidirectional"))
    )
    (net (code "109") (name "/{slash}RESET1") (class "Default")
      (node (ref "C14") (pin "2") (pinfunction "2_2") (pintype "passive"))
      (node (ref "P6") (pin "5") (pinfunction "5_5") (pintype "passive"))
      (node (ref "R31") (pin "1") (pinfunction "1_1") (pintype "passive"))
      (node (ref "U10") (pin "7") (pinfunction "/RESET_7") (pintype "passive"))
    )
    (net (code "110") (name "/~{RST}") (class "Default")
      (node (ref "U2") (pin "4") (pinfunction "PC15/OSC32_OUT_4") (pintype "passive"))
    )
    (net (code "111") (name "GND") (class "Default")
      (node (ref "C1") (pin "1") (pinfunction "1_1") (pintype "passive"))
      (node (ref "C11") (pin "1") (pinfunction "1_1") (pintype "passive"))
      (node (ref "C12") (pin "1") (pinfunction "1_1") (pintype "passive"))
      (node (ref "C14") (pin "1") (pinfunction "1_1") (pintype "passive"))
      (node (ref "C15") (pin "1") (pinfunction "1_1") (pintype "passive"))
      (node (ref "C16") (pin "1") (pinfunction "1_1") (pintype "passive"))
      (node (ref "C17") (pin "1") (pinfunction "1_1") (pintype "passive"))
      (node (ref "C18") (pin "1") (pinfunction "1_1") (pintype "passive"))
      (node (ref "C19") (pin "1") (pinfunction "1_1") (pintype "passive"))
      (node (ref "C2") (pin "1") (pinfunction "1_1") (pintype "passive"))
      (node (ref "C20") (pin "1") (pinfunction "1_1") (pintype "passive"))
      (node (ref "C21") (pin "1") (pinfunction "1_1") (pintype "passive"))
      (node (ref "C22") (pin "1") (pinfunction "1_1") (pintype "passive"))
      (node (ref "C23") (pin "1") (pinfunction "1_1") (pintype "passive"))
      (node (ref "C27") (pin "1") (pinfunction "1_1") (pintype "passive"))
      (node (ref "C28") (pin "1") (pinfunction "1_1") (pintype "passive"))
      (node (ref "C3") (pin "2") (pinfunction "2_2") (pintype "passive"))
      (node (ref "C4") (pin "2") (pinfunction "2_2") (pintype "passive"))
      (node (ref "C5") (pin "2") (pinfunction "2_2") (pintype "passive"))
      (node (ref "C6") (pin "2") (pinfunction "2_2") (pintype "passive"))
      (node (ref "C7") (pin "1") (pinfunction "1_1") (pintype "passive"))
      (node (ref "C8") (pin "2") (pinfunction "2_2") (pintype "passive"))
      (node (ref "CA1") (pin "2") (pinfunction "2_2") (pintype "passive"))
      (node (ref "CA2") (pin "2") (pinfunction "2_2") (pintype "passive"))
      (node (ref "JP2") (pin "24") (pinfunction "24_24") (pintype "passive"))
      (node (ref "JP2") (pin "26") (pinfunction "26_26") (pintype "passive"))
      (node (ref "K0") (pin "1") (pintype "passive"))
      (node (ref "K0") (pin "4") (pintype "passive"))
      (node (ref "LED1") (pin "2") (pinfunction "K_2") (pintype "passive"))
      (node (ref "P1") (pin "10") (pinfunction "10_10") (pintype "passive"))
      (node (ref "P1") (pin "11") (pinfunction "11_11") (pintype "passive"))
      (node (ref "P1") (pin "12") (pinfunction "12_12") (pintype "passive"))
      (node (ref "P1") (pin "14") (pinfunction "14_14") (pintype "passive"))
      (node (ref "P1") (pin "16") (pinfunction "16_16") (pintype "passive"))
      (node (ref "P1") (pin "18") (pinfunction "18_18") (pintype "passive"))
      (node (ref "P1") (pin "20") (pinfunction "20_20") (pintype "passive"))
      (node (ref "P1") (pin "4") (pinfunction "4_4") (pintype "passive"))
      (node (ref "P1") (pin "6") (pinfunction "6_6") (pintype "passive"))
      (node (ref "P1") (pin "8") (pinfunction "8_8") (pintype "passive"))
      (node (ref "P2") (pin "10") (pinfunction "10_10") (pintype "passive"))
      (node (ref "P2") (pin "2") (pinfunction "2_2") (pintype "passive"))
      (node (ref "P3") (pin "1") (pinfunction "1_1") (pintype "passive"))
      (node (ref "P3") (pin "2") (pinfunction "2_2") (pintype "passive"))
      (node (ref "P4") (pin "1") (pinfunction "1_1") (pintype "passive"))
      (node (ref "P4") (pin "2") (pinfunction "2_2") (pintype "passive"))
      (node (ref "P4") (pin "43") (pinfunction "43_43") (pintype "passive"))
      (node (ref "P4") (pin "44") (pinfunction "44_44") (pintype "passive"))
      (node (ref "P4") (pin "45") (pinfunction "45_45") (pintype "passive"))
      (node (ref "P4") (pin "46") (pinfunction "46_46") (pintype "passive"))
      (node (ref "P5") (pin "2") (pinfunction "2_2") (pintype "passive"))
      (node (ref "P6") (pin "6") (pinfunction "6_6") (pintype "passive"))
      (node (ref "R3") (pin "1") (pinfunction "1_1") (pintype "passive"))
      (node (ref "R4") (pin "1") (pinfunction "1_1") (pintype "passive"))
      (node (ref "R60") (pin "1") (pinfunction "1_1") (pintype "passive"))
      (node (ref "U1") (pin "1") (pinfunction "GND_1") (pintype "passive"))
      (node (ref "U10") (pin "30") (pinfunction "GND_30") (pintype "passive"))
      (node (ref "U10") (pin "31") (pinfunction "GND_31") (pintype "passive"))
      (node (ref "U10") (pin "32") (pinfunction "GND_32") (pintype "passive"))
      (node (ref "U2") (pin "12") (pinfunction "VSSA_12") (pintype "passive"))
      (node (ref "U2") (pin "18") (pinfunction "VSS_4_18") (pintype "passive"))
      (node (ref "U2") (pin "31") (pinfunction "VSS_1_31") (pintype "passive"))
      (node (ref "U2") (pin "47") (pinfunction "VSS_2_47") (pintype "passive"))
      (node (ref "U2") (pin "63") (pinfunction "VSS_3_63") (pintype "passive"))
      (node (ref "U3") (pin "10") (pinfunction "GNDIO_10") (pintype "power_in"))
      (node (ref "U3") (pin "11") (pinfunction "GNDINT_11") (pintype "power_in"))
      (node (ref "U3") (pin "32") (pinfunction "GNDIO_32") (pintype "power_in"))
      (node (ref "U3") (pin "46") (pinfunction "GNDIO_46") (pintype "power_in"))
      (node (ref "U3") (pin "60") (pinfunction "GNDIO_60") (pintype "power_in"))
      (node (ref "U3") (pin "65") (pinfunction "GNDINT_65") (pintype "power_in"))
      (node (ref "U3") (pin "79") (pinfunction "GNDIO_79") (pintype "power_in"))
      (node (ref "U3") (pin "93") (pinfunction "GNDIO_93") (pintype "power_in"))
      (node (ref "U6") (pin "2") (pinfunction "GND_2") (pintype "passive"))
    )
    (net (code "112") (name "Net-(D19-K)") (class "Default")
      (node (ref "D19") (pin "2") (pinfunction "K_2") (pintype "passive"))
      (node (ref "R35") (pin "2") (pinfunction "2_2") (pintype "passive"))
    )
    (net (code "113") (name "Net-(LED1-A)") (class "Default")
      (node (ref "LED1") (pin "1") (pinfunction "A_1") (pintype "passive"))
      (node (ref "R67") (pin "1") (pinfunction "1_1") (pintype "passive"))
    )
    (net (code "114") (name "Net-(RP1-Pad2)") (class "Default")
      (node (ref "RP1") (pin "2") (pinfunction "2_2") (pintype "passive"))
      (node (ref "U3") (pin "76") (pinfunction "IO_76") (pintype "bidirectional"))
    )
    (net (code "115") (name "Net-(RP1-Pad4)") (class "Default")
      (node (ref "RP1") (pin "4") (pinfunction "4_4") (pintype "passive"))
      (node (ref "U3") (pin "77") (pinfunction "IO_77") (pintype "bidirectional"))
    )
    (net (code "116") (name "Net-(RP1-Pad6)") (class "Default")
      (node (ref "RP1") (pin "6") (pinfunction "6_6") (pintype "passive"))
      (node (ref "U3") (pin "78") (pinfunction "IO_78") (pintype "bidirectional"))
    )
    (net (code "117") (name "Net-(RP1-Pad8)") (class "Default")
      (node (ref "RP1") (pin "8") (pinfunction "8_8") (pintype "passive"))
      (node (ref "U3") (pin "81") (pinfunction "IO_81") (pintype "bidirectional"))
    )
    (net (code "118") (name "Net-(RP2-Pad2)") (class "Default")
      (node (ref "RP2") (pin "2") (pinfunction "2_2") (pintype "passive"))
      (node (ref "U3") (pin "82") (pinfunction "IO_82") (pintype "bidirectional"))
    )
    (net (code "119") (name "Net-(RP2-Pad4)") (class "Default")
      (node (ref "RP2") (pin "4") (pinfunction "4_4") (pintype "passive"))
      (node (ref "U3") (pin "83") (pinfunction "IO_83") (pintype "bidirectional"))
    )
    (net (code "120") (name "Net-(RP2-Pad6)") (class "Default")
      (node (ref "RP2") (pin "6") (pinfunction "6_6") (pintype "passive"))
      (node (ref "U3") (pin "84") (pinfunction "IO_84") (pintype "bidirectional"))
    )
    (net (code "121") (name "Net-(RP2-Pad8)") (class "Default")
      (node (ref "RP2") (pin "8") (pinfunction "8_8") (pintype "passive"))
      (node (ref "U3") (pin "85") (pinfunction "IO_85") (pintype "bidirectional"))
    )
    (net (code "122") (name "Net-(RP3-Pad2)") (class "Default")
      (node (ref "RP3") (pin "2") (pinfunction "2_2") (pintype "passive"))
      (node (ref "U3") (pin "86") (pinfunction "IO_86") (pintype "bidirectional"))
    )
    (net (code "123") (name "Net-(RP3-Pad4)") (class "Default")
      (node (ref "RP3") (pin "4") (pinfunction "4_4") (pintype "passive"))
      (node (ref "U3") (pin "87") (pinfunction "IO_87") (pintype "bidirectional"))
    )
    (net (code "124") (name "Net-(RP3-Pad6)") (class "Default")
      (node (ref "RP3") (pin "6") (pinfunction "6_6") (pintype "passive"))
      (node (ref "U3") (pin "88") (pinfunction "IO_88") (pintype "bidirectional"))
    )
    (net (code "125") (name "Net-(RP3-Pad8)") (class "Default")
      (node (ref "RP3") (pin "8") (pinfunction "8_8") (pintype "passive"))
      (node (ref "U3") (pin "89") (pinfunction "IO_89") (pintype "bidirectional"))
    )
    (net (code "126") (name "Net-(RP4-Pad2)") (class "Default")
      (node (ref "RP4") (pin "2") (pinfunction "2_2") (pintype "passive"))
      (node (ref "U3") (pin "90") (pinfunction "IO_90") (pintype "bidirectional"))
    )
    (net (code "127") (name "Net-(RP4-Pad4)") (class "Default")
      (node (ref "RP4") (pin "4") (pinfunction "4_4") (pintype "passive"))
      (node (ref "U3") (pin "91") (pinfunction "IO_91") (pintype "bidirectional"))
    )
    (net (code "128") (name "Net-(RP4-Pad6)") (class "Default")
      (node (ref "RP4") (pin "6") (pinfunction "6_6") (pintype "passive"))
      (node (ref "U3") (pin "92") (pinfunction "IO_92") (pintype "bidirectional"))
    )
    (net (code "129") (name "Net-(RP4-Pad8)") (class "Default")
      (node (ref "RP4") (pin "8") (pinfunction "8_8") (pintype "passive"))
      (node (ref "U3") (pin "95") (pinfunction "IO_95") (pintype "bidirectional"))
    )
    (net (code "130") (name "Net-(RP5-Pad2)") (class "Default")
      (node (ref "RP5") (pin "2") (pinfunction "2_2") (pintype "passive"))
      (node (ref "U3") (pin "96") (pinfunction "IO_96") (pintype "bidirectional"))
    )
    (net (code "131") (name "Net-(RP5-Pad4)") (class "Default")
      (node (ref "RP5") (pin "4") (pinfunction "4_4") (pintype "passive"))
      (node (ref "U3") (pin "97") (pinfunction "IO_97") (pintype "bidirectional"))
    )
    (net (code "132") (name "Net-(RP5-Pad6)") (class "Default")
      (node (ref "RP5") (pin "6") (pinfunction "6_6") (pintype "passive"))
      (node (ref "U3") (pin "98") (pinfunction "IO_98") (pintype "bidirectional"))
    )
    (net (code "133") (name "Net-(RP5-Pad8)") (class "Default")
      (node (ref "RP5") (pin "8") (pinfunction "8_8") (pintype "passive"))
      (node (ref "U3") (pin "99") (pinfunction "IO_99") (pintype "bidirectional"))
    )
    (net (code "134") (name "Net-(U2-PA4{slash}SPI1_NSS{slash}DAC_OUT1{slash}USART2_CK{slash}ADC12_IN4)") (class "Default")
      (node (ref "RP8") (pin "2") (pinfunction "2_2") (pintype "passive"))
      (node (ref "U2") (pin "20") (pinfunction "PA4/SPI1_NSS/DAC_OUT1/USART2_CK/ADC12_IN4_20") (pintype "passive"))
    )
    (net (code "135") (name "Net-(U2-PA5{slash}SPI1_SCK{slash}DAC_OUT2{slash}ADC12_IN5)") (class "Default")
      (node (ref "RP8") (pin "4") (pinfunction "4_4") (pintype "passive"))
      (node (ref "U2") (pin "21") (pinfunction "PA5/SPI1_SCK/DAC_OUT2/ADC12_IN5_21") (pintype "passive"))
    )
    (net (code "136") (name "Net-(U2-PA6{slash}SPI1_MISO{slash}TIM8_BKIN{slash}ADC12_IN6{slash}TIM3_CH1)") (class "Default")
      (node (ref "RP8") (pin "6") (pinfunction "6_6") (pintype "passive"))
      (node (ref "U2") (pin "22") (pinfunction "PA6/SPI1_MISO/TIM8_BKIN/ADC12_IN6/TIM3_CH1_22") (pintype "passive"))
    )
    (net (code "137") (name "Net-(U2-PA7{slash}SPI1_MOSI{slash}TIM8_CH1N{slash}ADC12_IN7{slash}TIM3_CH2)") (class "Default")
      (node (ref "RP8") (pin "8") (pinfunction "8_8") (pintype "passive"))
      (node (ref "U2") (pin "23") (pinfunction "PA7/SPI1_MOSI/TIM8_CH1N/ADC12_IN7/TIM3_CH2_23") (pintype "passive"))
    )
    (net (code "138") (name "Net-(U2-PA8{slash}USART1_CK{slash}TIM1_CH1{slash}MCO)") (class "Default")
      (node (ref "R18") (pin "2") (pinfunction "2_2") (pintype "passive"))
      (node (ref "U2") (pin "41") (pinfunction "PA8/USART1_CK/TIM1_CH1/MCO_41") (pintype "passive"))
    )
    (net (code "139") (name "Net-(U2-PC0{slash}ADC123_IN10)") (class "Default")
      (node (ref "RP6") (pin "2") (pinfunction "2_2") (pintype "passive"))
      (node (ref "U2") (pin "8") (pinfunction "PC0/ADC123_IN10_8") (pintype "passive"))
    )
    (net (code "140") (name "Net-(U2-PC1{slash}ADC123_IN11)") (class "Default")
      (node (ref "RP6") (pin "4") (pinfunction "4_4") (pintype "passive"))
      (node (ref "U2") (pin "9") (pinfunction "PC1/ADC123_IN11_9") (pintype "passive"))
    )
    (net (code "141") (name "Net-(U2-PC2{slash}ADC123_IN12)") (class "Default")
      (node (ref "RP6") (pin "6") (pinfunction "6_6") (pintype "passive"))
      (node (ref "U2") (pin "10") (pinfunction "PC2/ADC123_IN12_10") (pintype "passive"))
    )
    (net (code "142") (name "Net-(U2-PC3{slash}ADC123_IN13)") (class "Default")
      (node (ref "RP6") (pin "8") (pinfunction "8_8") (pintype "passive"))
      (node (ref "U2") (pin "11") (pinfunction "PC3/ADC123_IN13_11") (pintype "passive"))
    )
    (net (code "143") (name "Net-(U2-PC4{slash}ADC12_IN14)") (class "Default")
      (node (ref "RP7") (pin "2") (pinfunction "2_2") (pintype "passive"))
      (node (ref "U2") (pin "24") (pinfunction "PC4/ADC12_IN14_24") (pintype "passive"))
    )
    (net (code "144") (name "Net-(U2-PC5{slash}ADC12_IN15)") (class "Default")
      (node (ref "RP7") (pin "4") (pinfunction "4_4") (pintype "passive"))
      (node (ref "U2") (pin "25") (pinfunction "PC5/ADC12_IN15_25") (pintype "passive"))
    )
    (net (code "145") (name "Net-(U2-PC6{slash}I2S2_MCK{slash}TIM8_CH1{slash}SDIO_D6)") (class "Default")
      (node (ref "RP7") (pin "6") (pinfunction "6_6") (pintype "passive"))
      (node (ref "U2") (pin "37") (pinfunction "PC6/I2S2_MCK/TIM8_CH1/SDIO_D6_37") (pintype "passive"))
    )
    (net (code "146") (name "Net-(U2-PC7{slash}I2S3_MCK{slash}TIM8_CH2{slash}SDIO_D7)") (class "Default")
      (node (ref "RP7") (pin "8") (pinfunction "8_8") (pintype "passive"))
      (node (ref "U2") (pin "38") (pinfunction "PC7/I2S3_MCK/TIM8_CH2/SDIO_D7_38") (pintype "passive"))
    )
    (net (code "147") (name "Net-(U2-PD0{slash}OSC_IN{slash}FSMC_D2)") (class "Default")
      (node (ref "C11") (pin "2") (pinfunction "2_2") (pintype "passive"))
      (node (ref "U2") (pin "5") (pinfunction "PD0/OSC_IN/FSMC_D2_5") (pintype "passive"))
      (node (ref "Y1") (pin "2") (pinfunction "OSC2_2") (pintype "passive"))
    )
    (net (code "148") (name "Net-(U2-PD1{slash}OSC_OUT{slash}FSMC_D3)") (class "Default")
      (node (ref "C8") (pin "1") (pinfunction "1_1") (pintype "passive"))
      (node (ref "U2") (pin "6") (pinfunction "PD1/OSC_OUT/FSMC_D3_6") (pintype "passive"))
      (node (ref "Y1") (pin "1") (pinfunction "OSC1_1") (pintype "passive"))
    )
    (net (code "149") (name "Net-(U6-OUT)") (class "Default")
      (node (ref "R59") (pin "2") (pinfunction "2_2") (pintype "passive"))
      (node (ref "U6") (pin "3") (pinfunction "OUT_3") (pintype "passive"))
    )
    (net (code "150") (name "Net-(U10-PA1)") (class "Default")
      (node (ref "R35") (pin "1") (pinfunction "1_1") (pintype "passive"))
      (node (ref "U10") (pin "11") (pinfunction "PA1_11") (pintype "passive"))
    )
    (net (code "151") (name "V3_3D") (class "Default")
      (node (ref "D19") (pin "1") (pinfunction "A_1") (pintype "passive"))
      (node (ref "P6") (pin "1") (pinfunction "1_1") (pintype "passive"))
      (node (ref "R29") (pin "1") (pinfunction "1_1") (pintype "passive"))
      (node (ref "R31") (pin "2") (pinfunction "2_2") (pintype "passive"))
      (node (ref "R33") (pin "1") (pinfunction "1_1") (pintype "passive"))
      (node (ref "R34") (pin "2") (pinfunction "2_2") (pintype "passive"))
      (node (ref "U10") (pin "1") (pinfunction "3.3V_1") (pintype "passive"))
      (node (ref "U10") (pin "2") (pinfunction "3.3V_2") (pintype "passive"))
    )
    (net (code "152") (name "VCC3V3") (class "Default")
      (node (ref "C1") (pin "2") (pinfunction "2_2") (pintype "passive"))
      (node (ref "C16") (pin "2") (pinfunction "2_2") (pintype "passive"))
      (node (ref "C17") (pin "2") (pinfunction "2_2") (pintype "passive"))
      (node (ref "C18") (pin "2") (pinfunction "2_2") (pintype "passive"))
      (node (ref "C19") (pin "2") (pinfunction "2_2") (pintype "passive"))
      (node (ref "C20") (pin "2") (pinfunction "2_2") (pintype "passive"))
      (node (ref "C21") (pin "2") (pinfunction "2_2") (pintype "passive"))
      (node (ref "C22") (pin "2") (pinfunction "2_2") (pintype "passive"))
      (node (ref "C23") (pin "2") (pinfunction "2_2") (pintype "passive"))
      (node (ref "C27") (pin "2") (pinfunction "2_2") (pintype "passive"))
      (node (ref "C3") (pin "1") (pinfunction "1_1") (pintype "passive"))
      (node (ref "C4") (pin "1") (pinfunction "1_1") (pintype "passive"))
      (node (ref "C5") (pin "1") (pinfunction "1_1") (pintype "passive"))
      (node (ref "C6") (pin "1") (pinfunction "1_1") (pintype "passive"))
      (node (ref "CA1") (pin "1") (pinfunction "1_1") (pintype "passive"))
      (node (ref "JP2") (pin "23") (pinfunction "23_23") (pintype "passive"))
      (node (ref "JP2") (pin "25") (pinfunction "25_25") (pintype "passive"))
      (node (ref "P1") (pin "1") (pinfunction "1_1") (pintype "passive"))
      (node (ref "P1") (pin "2") (pinfunction "2_2") (pintype "passive"))
      (node (ref "P2") (pin "4") (pinfunction "4_4") (pintype "passive"))
      (node (ref "R1") (pin "2") (pinfunction "2_2") (pintype "passive"))
      (node (ref "R2") (pin "1") (pinfunction "1_1") (pintype "passive"))
      (node (ref "R56") (pin "2") (pinfunction "2_2") (pintype "passive"))
      (node (ref "R57") (pin "2") (pinfunction "2_2") (pintype "passive"))
      (node (ref "R58") (pin "2") (pinfunction "2_2") (pintype "passive"))
      (node (ref "R67") (pin "2") (pinfunction "2_2") (pintype "passive"))
      (node (ref "U1") (pin "2") (pinfunction "OUT_2") (pintype "passive"))
      (node (ref "U2") (pin "1") (pinfunction "VBAT_1") (pintype "passive"))
      (node (ref "U2") (pin "13") (pinfunction "VDDA_13") (pintype "passive"))
      (node (ref "U2") (pin "19") (pinfunction "VDD_4_19") (pintype "passive"))
      (node (ref "U2") (pin "32") (pinfunction "VDD_1_32") (pintype "passive"))
      (node (ref "U2") (pin "48") (pinfunction "VDD_2_48") (pintype "passive"))
      (node (ref "U2") (pin "64") (pinfunction "VDD_3_64") (pintype "passive"))
      (node (ref "U3") (pin "13") (pinfunction "VCCINT_13") (pintype "power_in"))
      (node (ref "U3") (pin "31") (pinfunction "VCCIO1_31") (pintype "power_in"))
      (node (ref "U3") (pin "45") (pinfunction "VCCIO1_45") (pintype "power_in"))
      (node (ref "U3") (pin "59") (pinfunction "VCCIO2_59") (pintype "power_in"))
      (node (ref "U3") (pin "63") (pinfunction "VCCINT_63") (pintype "power_in"))
      (node (ref "U3") (pin "80") (pinfunction "VCCIO2_80") (pintype "power_in"))
      (node (ref "U3") (pin "9") (pinfunction "VCCIO1_9") (pintype "power_in"))
      (node (ref "U3") (pin "94") (pinfunction "VCCIO2_94") (pintype "power_in"))
      (node (ref "U6") (pin "4") (pinfunction "VCC_4") (pintype "passive"))
    )
    (net (code "153") (name "VDD_5V") (class "Default")
      (node (ref "C2") (pin "2") (pinfunction "2_2") (pintype "passive"))
      (node (ref "CA2") (pin "1") (pinfunction "1_1") (pintype "passive"))
      (node (ref "JP2") (pin "21") (pinfunction "21_21") (pintype "passive"))
      (node (ref "JP2") (pin "22") (pinfunction "22_22") (pintype "passive"))
      (node (ref "P4") (pin "5") (pinfunction "5_5") (pintype "passive"))
      (node (ref "P4") (pin "6") (pinfunction "6_6") (pintype "passive"))
      (node (ref "U1") (pin "3") (pinfunction "IN_3") (pintype "passive"))
    )
    (net (code "154") (name "unconnected-(P1-Pad17)") (class "Default")
      (node (ref "P1") (pin "17") (pinfunction "17_17") (pintype "passive+no_connect"))
    )
    (net (code "155") (name "unconnected-(P1-Pad19)") (class "Default")
      (node (ref "P1") (pin "19") (pinfunction "19_19") (pintype "passive+no_connect"))
    )
    (net (code "156") (name "unconnected-(P2-Pad6)") (class "Default")
      (node (ref "P2") (pin "6") (pinfunction "6_6") (pintype "passive+no_connect"))
    )
    (net (code "157") (name "unconnected-(P2-Pad7)") (class "Default")
      (node (ref "P2") (pin "7") (pinfunction "7_7") (pintype "passive+no_connect"))
    )
    (net (code "158") (name "unconnected-(P2-Pad8)") (class "Default")
      (node (ref "P2") (pin "8") (pinfunction "8_8") (pintype "passive+no_connect"))
    )
    (net (code "159") (name "unconnected-(P3-Pad3)") (class "Default")
      (node (ref "P3") (pin "3") (pinfunction "3_3") (pintype "passive"))
    )
    (net (code "160") (name "unconnected-(P3-Pad4)") (class "Default")
      (node (ref "P3") (pin "4") (pinfunction "4_4") (pintype "passive"))
    )
    (net (code "161") (name "unconnected-(P3-Pad5)") (class "Default")
      (node (ref "P3") (pin "5") (pinfunction "5_5") (pintype "passive"))
    )
    (net (code "162") (name "unconnected-(P3-Pad6)") (class "Default")
      (node (ref "P3") (pin "6") (pinfunction "6_6") (pintype "passive"))
    )
    (net (code "163") (name "unconnected-(P3-Pad22)") (class "Default")
      (node (ref "P3") (pin "22") (pinfunction "22_22") (pintype "passive"))
    )
    (net (code "164") (name "unconnected-(P3-Pad23)") (class "Default")
      (node (ref "P3") (pin "23") (pinfunction "23_23") (pintype "passive"))
    )
    (net (code "165") (name "unconnected-(P3-Pad24)") (class "Default")
      (node (ref "P3") (pin "24") (pinfunction "24_24") (pintype "passive"))
    )
    (net (code "166") (name "unconnected-(P3-Pad25)") (class "Default")
      (node (ref "P3") (pin "25") (pinfunction "25_25") (pintype "passive"))
    )
    (net (code "167") (name "unconnected-(P3-Pad27)") (class "Default")
      (node (ref "P3") (pin "27") (pinfunction "27_27") (pintype "passive"))
    )
    (net (code "168") (name "unconnected-(P3-Pad28)") (class "Default")
      (node (ref "P3") (pin "28") (pinfunction "28_28") (pintype "passive"))
    )
    (net (code "169") (name "unconnected-(P3-Pad29)") (class "Default")
      (node (ref "P3") (pin "29") (pinfunction "29_29") (pintype "passive"))
    )
    (net (code "170") (name "unconnected-(P3-Pad30)") (class "Default")
      (node (ref "P3") (pin "30") (pinfunction "30_30") (pintype "passive"))
    )
    (net (code "171") (name "unconnected-(P3-Pad31)") (class "Default")
      (node (ref "P3") (pin "31") (pinfunction "31_31") (pintype "passive"))
    )
    (net (code "172") (name "unconnected-(P3-Pad32)") (class "Default")
      (node (ref "P3") (pin "32") (pinfunction "32_32") (pintype "passive"))
    )
    (net (code "173") (name "unconnected-(P3-Pad33)") (class "Default")
      (node (ref "P3") (pin "33") (pinfunction "33_33") (pintype "passive"))
    )
    (net (code "174") (name "unconnected-(P3-Pad34)") (class "Default")
      (node (ref "P3") (pin "34") (pinfunction "34_34") (pintype "passive"))
    )
    (net (code "175") (name "unconnected-(P3-Pad35)") (class "Default")
      (node (ref "P3") (pin "35") (pinfunction "35_35") (pintype "passive"))
    )
    (net (code "176") (name "unconnected-(P3-Pad36)") (class "Default")
      (node (ref "P3") (pin "36") (pinfunction "36_36") (pintype "passive"))
    )
    (net (code "177") (name "unconnected-(P3-Pad37)") (class "Default")
      (node (ref "P3") (pin "37") (pinfunction "37_37") (pintype "passive"))
    )
    (net (code "178") (name "unconnected-(P3-Pad38)") (class "Default")
      (node (ref "P3") (pin "38") (pinfunction "38_38") (pintype "passive"))
    )
    (net (code "179") (name "unconnected-(P3-Pad39)") (class "Default")
      (node (ref "P3") (pin "39") (pinfunction "39_39") (pintype "passive"))
    )
    (net (code "180") (name "unconnected-(P3-Pad40)") (class "Default")
      (node (ref "P3") (pin "40") (pinfunction "40_40") (pintype "passive"))
    )
    (net (code "181") (name "unconnected-(P3-Pad41)") (class "Default")
      (node (ref "P3") (pin "41") (pinfunction "41_41") (pintype "passive"))
    )
    (net (code "182") (name "unconnected-(P3-Pad42)") (class "Default")
      (node (ref "P3") (pin "42") (pinfunction "42_42") (pintype "passive"))
    )
    (net (code "183") (name "unconnected-(P3-Pad43)") (class "Default")
      (node (ref "P3") (pin "43") (pinfunction "43_43") (pintype "passive"))
    )
    (net (code "184") (name "unconnected-(P3-Pad44)") (class "Default")
      (node (ref "P3") (pin "44") (pinfunction "44_44") (pintype "passive"))
    )
    (net (code "185") (name "unconnected-(P3-Pad45)") (class "Default")
      (node (ref "P3") (pin "45") (pinfunction "45_45") (pintype "passive"))
    )
    (net (code "186") (name "unconnected-(P3-Pad46)") (class "Default")
      (node (ref "P3") (pin "46") (pinfunction "46_46") (pintype "passive"))
    )
    (net (code "187") (name "unconnected-(P4-Pad3)") (class "Default")
      (node (ref "P4") (pin "3") (pinfunction "3_3") (pintype "passive"))
    )
    (net (code "188") (name "unconnected-(P4-Pad4)") (class "Default")
      (node (ref "P4") (pin "4") (pinfunction "4_4") (pintype "passive"))
    )
    (net (code "189") (name "unconnected-(P4-Pad7)") (class "Default")
      (node (ref "P4") (pin "7") (pinfunction "7_7") (pintype "passive"))
    )
    (net (code "190") (name "unconnected-(P4-Pad8)") (class "Default")
      (node (ref "P4") (pin "8") (pinfunction "8_8") (pintype "passive"))
    )
    (net (code "191") (name "unconnected-(P4-Pad9)") (class "Default")
      (node (ref "P4") (pin "9") (pinfunction "9_9") (pintype "passive"))
    )
    (net (code "192") (name "unconnected-(P4-Pad10)") (class "Default")
      (node (ref "P4") (pin "10") (pinfunction "10_10") (pintype "passive"))
    )
    (net (code "193") (name "unconnected-(P4-Pad28)") (class "Default")
      (node (ref "P4") (pin "28") (pinfunction "28_28") (pintype "passive"))
    )
    (net (code "194") (name "unconnected-(P4-Pad29)") (class "Default")
      (node (ref "P4") (pin "29") (pinfunction "29_29") (pintype "passive"))
    )
    (net (code "195") (name "unconnected-(P4-Pad30)") (class "Default")
      (node (ref "P4") (pin "30") (pinfunction "30_30") (pintype "passive"))
    )
    (net (code "196") (name "unconnected-(P4-Pad31)") (class "Default")
      (node (ref "P4") (pin "31") (pinfunction "31_31") (pintype "passive"))
    )
    (net (code "197") (name "unconnected-(P4-Pad32)") (class "Default")
      (node (ref "P4") (pin "32") (pinfunction "32_32") (pintype "passive"))
    )
    (net (code "198") (name "unconnected-(P4-Pad33)") (class "Default")
      (node (ref "P4") (pin "33") (pinfunction "33_33") (pintype "passive"))
    )
    (net (code "199") (name "unconnected-(P4-Pad34)") (class "Default")
      (node (ref "P4") (pin "34") (pinfunction "34_34") (pintype "passive"))
    )
    (net (code "200") (name "unconnected-(P4-Pad35)") (class "Default")
      (node (ref "P4") (pin "35") (pinfunction "35_35") (pintype "passive"))
    )
    (net (code "201") (name "unconnected-(P4-Pad36)") (class "Default")
      (node (ref "P4") (pin "36") (pinfunction "36_36") (pintype "passive"))
    )
    (net (code "202") (name "unconnected-(P4-Pad37)") (class "Default")
      (node (ref "P4") (pin "37") (pinfunction "37_37") (pintype "passive"))
    )
    (net (code "203") (name "unconnected-(P4-Pad38)") (class "Default")
      (node (ref "P4") (pin "38") (pinfunction "38_38") (pintype "passive"))
    )
    (net (code "204") (name "unconnected-(P4-Pad39)") (class "Default")
      (node (ref "P4") (pin "39") (pinfunction "39_39") (pintype "passive"))
    )
    (net (code "205") (name "unconnected-(P4-Pad40)") (class "Default")
      (node (ref "P4") (pin "40") (pinfunction "40_40") (pintype "passive"))
    )
    (net (code "206") (name "unconnected-(P4-Pad42)") (class "Default")
      (node (ref "P4") (pin "42") (pinfunction "42_42") (pintype "passive"))
    )
    (net (code "207") (name "unconnected-(P5-Pad3)") (class "Default")
      (node (ref "P5") (pin "3") (pinfunction "3_3") (pintype "passive"))
    )
    (net (code "208") (name "unconnected-(P5-Pad4)") (class "Default")
      (node (ref "P5") (pin "4") (pinfunction "4_4") (pintype "passive"))
    )
    (net (code "209") (name "unconnected-(U2-PB0{slash}ADC12_IN8{slash}TIM3_CH3{slash}TIM8_CH2N-Pad26)") (class "Default")
      (node (ref "U2") (pin "26") (pinfunction "PB0/ADC12_IN8/TIM3_CH3/TIM8_CH2N_26") (pintype "passive+no_connect"))
    )
    (net (code "210") (name "unconnected-(U2-PB1{slash}ADC12_IN9{slash}TIM3_CH4{slash}TIM8_CH3N-Pad27)") (class "Default")
      (node (ref "U2") (pin "27") (pinfunction "PB1/ADC12_IN9/TIM3_CH4/TIM8_CH3N_27") (pintype "passive"))
    )
    (net (code "211") (name "unconnected-(U2-PB5{slash}I2C1_SMBAI{slash}SPI3_MOSI{slash}I2S3_SD-Pad57)") (class "Default")
      (node (ref "U2") (pin "57") (pinfunction "PB5/I2C1_SMBAI/SPI3_MOSI/I2S3_SD_57") (pintype "passive+no_connect"))
    )
    (net (code "212") (name "unconnected-(U2-PB8{slash}TIM4_CH3{slash}SDIO_D4-Pad61)") (class "Default")
      (node (ref "U2") (pin "61") (pinfunction "PB8/TIM4_CH3/SDIO_D4_61") (pintype "passive+no_connect"))
    )
    (net (code "213") (name "unconnected-(U2-PB9{slash}TIM4_CH4{slash}SDIO_D5-Pad62)") (class "Default")
      (node (ref "U2") (pin "62") (pinfunction "PB9/TIM4_CH4/SDIO_D5_62") (pintype "passive+no_connect"))
    )
    (net (code "214") (name "unconnected-(U2-PB13{slash}SPI2_SCK{slash}I2S2_CK{slash}USART3_CTS{slash}TIM1_CH1N-Pad34)") (class "Default")
      (node (ref "U2") (pin "34") (pinfunction "PB13/SPI2_SCK/I2S2_CK/USART3_CTS/TIM1_CH1N_34") (pintype "passive"))
    )
    (net (code "215") (name "unconnected-(U2-PB14{slash}SPI2_MISO{slash}TIM1_CH2N{slash}USART3_RTS-Pad35)") (class "Default")
      (node (ref "U2") (pin "35") (pinfunction "PB14/SPI2_MISO/TIM1_CH2N/USART3_RTS_35") (pintype "passive"))
    )
    (net (code "216") (name "unconnected-(U2-PB15{slash}SPI2_MOSI{slash}I2S2_SD{slash}TIM1_CH3N-Pad36)") (class "Default")
      (node (ref "U2") (pin "36") (pinfunction "PB15/SPI2_MOSI/I2S2_SD/TIM1_CH3N_36") (pintype "passive"))
    )
    (net (code "217") (name "unconnected-(U2-PC12{slash}UART5_TX{slash}SDIO_CK-Pad53)") (class "Default")
      (node (ref "U2") (pin "53") (pinfunction "PC12/UART5_TX/SDIO_CK_53") (pintype "passive+no_connect"))
    )
    (net (code "218") (name "unconnected-(U2-PC14{slash}OSC32_IN-Pad3)") (class "Default")
      (node (ref "U2") (pin "3") (pinfunction "PC14/OSC32_IN_3") (pintype "passive+no_connect"))
    )
    (net (code "219") (name "unconnected-(U2-PD2{slash}TIM3_ETR{slash}UART5_RX{slash}SDIO_CMD-Pad54)") (class "Default")
      (node (ref "U2") (pin "54") (pinfunction "PD2/TIM3_ETR/UART5_RX/SDIO_CMD_54") (pintype "passive+no_connect"))
    )
    (net (code "220") (name "unconnected-(U3A-IO-Pad18)") (class "Default")
      (node (ref "U3") (pin "18") (pinfunction "IO_18") (pintype "bidirectional"))
    )
    (net (code "221") (name "unconnected-(U6-NC-Pad1)") (class "Default")
      (node (ref "U6") (pin "1") (pinfunction "NC_1") (pintype "passive+no_connect"))
    )
    (net (code "222") (name "unconnected-(U10-PA0-Pad10)") (class "Default")
      (node (ref "U10") (pin "10") (pinfunction "PA0_10") (pintype "passive"))
    )
    (net (code "223") (name "unconnected-(U10-PA2-Pad12)") (class "Default")
      (node (ref "U10") (pin "12") (pinfunction "PA2_12") (pintype "passive"))
    )
    (net (code "224") (name "unconnected-(U10-PA3-Pad13)") (class "Default")
      (node (ref "U10") (pin "13") (pinfunction "PA3_13") (pintype "passive"))
    )
    (net (code "225") (name "unconnected-(U10-PA4-Pad14)") (class "Default")
      (node (ref "U10") (pin "14") (pinfunction "PA4_14") (pintype "passive+no_connect"))
    )
    (net (code "226") (name "unconnected-(U10-PA7-Pad6)") (class "Default")
      (node (ref "U10") (pin "6") (pinfunction "PA7_6") (pintype "passive"))
    )
    (net (code "227") (name "unconnected-(U10-PB0-Pad23)") (class "Default")
      (node (ref "U10") (pin "23") (pinfunction "PB0_23") (pintype "passive+no_connect"))
    )
    (net (code "228") (name "unconnected-(U10-PB3-Pad8)") (class "Default")
      (node (ref "U10") (pin "8") (pinfunction "PB3_8") (pintype "passive+no_connect"))
    )
    (net (code "229") (name "unconnected-(U10-PB4-Pad9)") (class "Default")
      (node (ref "U10") (pin "9") (pinfunction "PB4_9") (pintype "passive+no_connect"))
    )
    (net (code "230") (name "unconnected-(U10-PB5-Pad28)") (class "Default")
      (node (ref "U10") (pin "28") (pinfunction "PB5_28") (pintype "passive"))
    )
    (net (code "231") (name "unconnected-(U10-PB6-Pad27)") (class "Default")
      (node (ref "U10") (pin "27") (pinfunction "PB6_27") (pintype "passive"))
    )
    (net (code "232") (name "unconnected-(U10-PB7-Pad26)") (class "Default")
      (node (ref "U10") (pin "26") (pinfunction "PB7_26") (pintype "passive+no_connect"))
    )
    (net (code "233") (name "unconnected-(U10-PC0-Pad25)") (class "Default")
      (node (ref "U10") (pin "25") (pinfunction "PC0_25") (pintype "passive+no_connect"))
    )
    (net (code "234") (name "unconnected-(U10-PC1-Pad24)") (class "Default")
      (node (ref "U10") (pin "24") (pinfunction "PC1_24") (pintype "passive+no_connect"))
    )
    (net (code "235") (name "unconnected-(U10-PC2-Pad17)") (class "Default")
      (node (ref "U10") (pin "17") (pinfunction "PC2_17") (pintype "passive+no_connect"))
    )
    (net (code "236") (name "unconnected-(U10-PC3-Pad21)") (class "Default")
      (node (ref "U10") (pin "21") (pinfunction "PC3_21") (pintype "passive+no_connect"))
    )
    (net (code "237") (name "unconnected-(U10-PC4-Pad22)") (class "Default")
      (node (ref "U10") (pin "22") (pinfunction "PC4_22") (pintype "passive+no_connect"))
    )
    (net (code "238") (name "unconnected-(U10-PC5-Pad3)") (class "Default")
      (node (ref "U10") (pin "3") (pinfunction "PC5_3") (pintype "passive+no_connect"))
    )
    (net (code "239") (name "unconnected-(U10-PC6-Pad4)") (class "Default")
      (node (ref "U10") (pin "4") (pinfunction "PC6_4") (pintype "passive"))
    )
    (net (code "240") (name "unconnected-(U10-PC7-Pad5)") (class "Default")
      (node (ref "U10") (pin "5") (pinfunction "PC7_5") (pintype "passive"))
    )
    (net (code "241") (name "unconnected-(U10-Pad29)") (class "Default")
      (node (ref "U10") (pin "29") (pintype "passive+no_connect"))
    )
    (net (code "242") (name "unconnected-(U10-SWCLK-Pad20)") (class "Default")
      (node (ref "U10") (pin "20") (pinfunction "SWCLK_20") (pintype "passive+no_connect"))
    )
  )
)
